# VoidX-Mini-Stomp-X.net
KiCad netlist of a schematic drawn in EasyEDA Pro
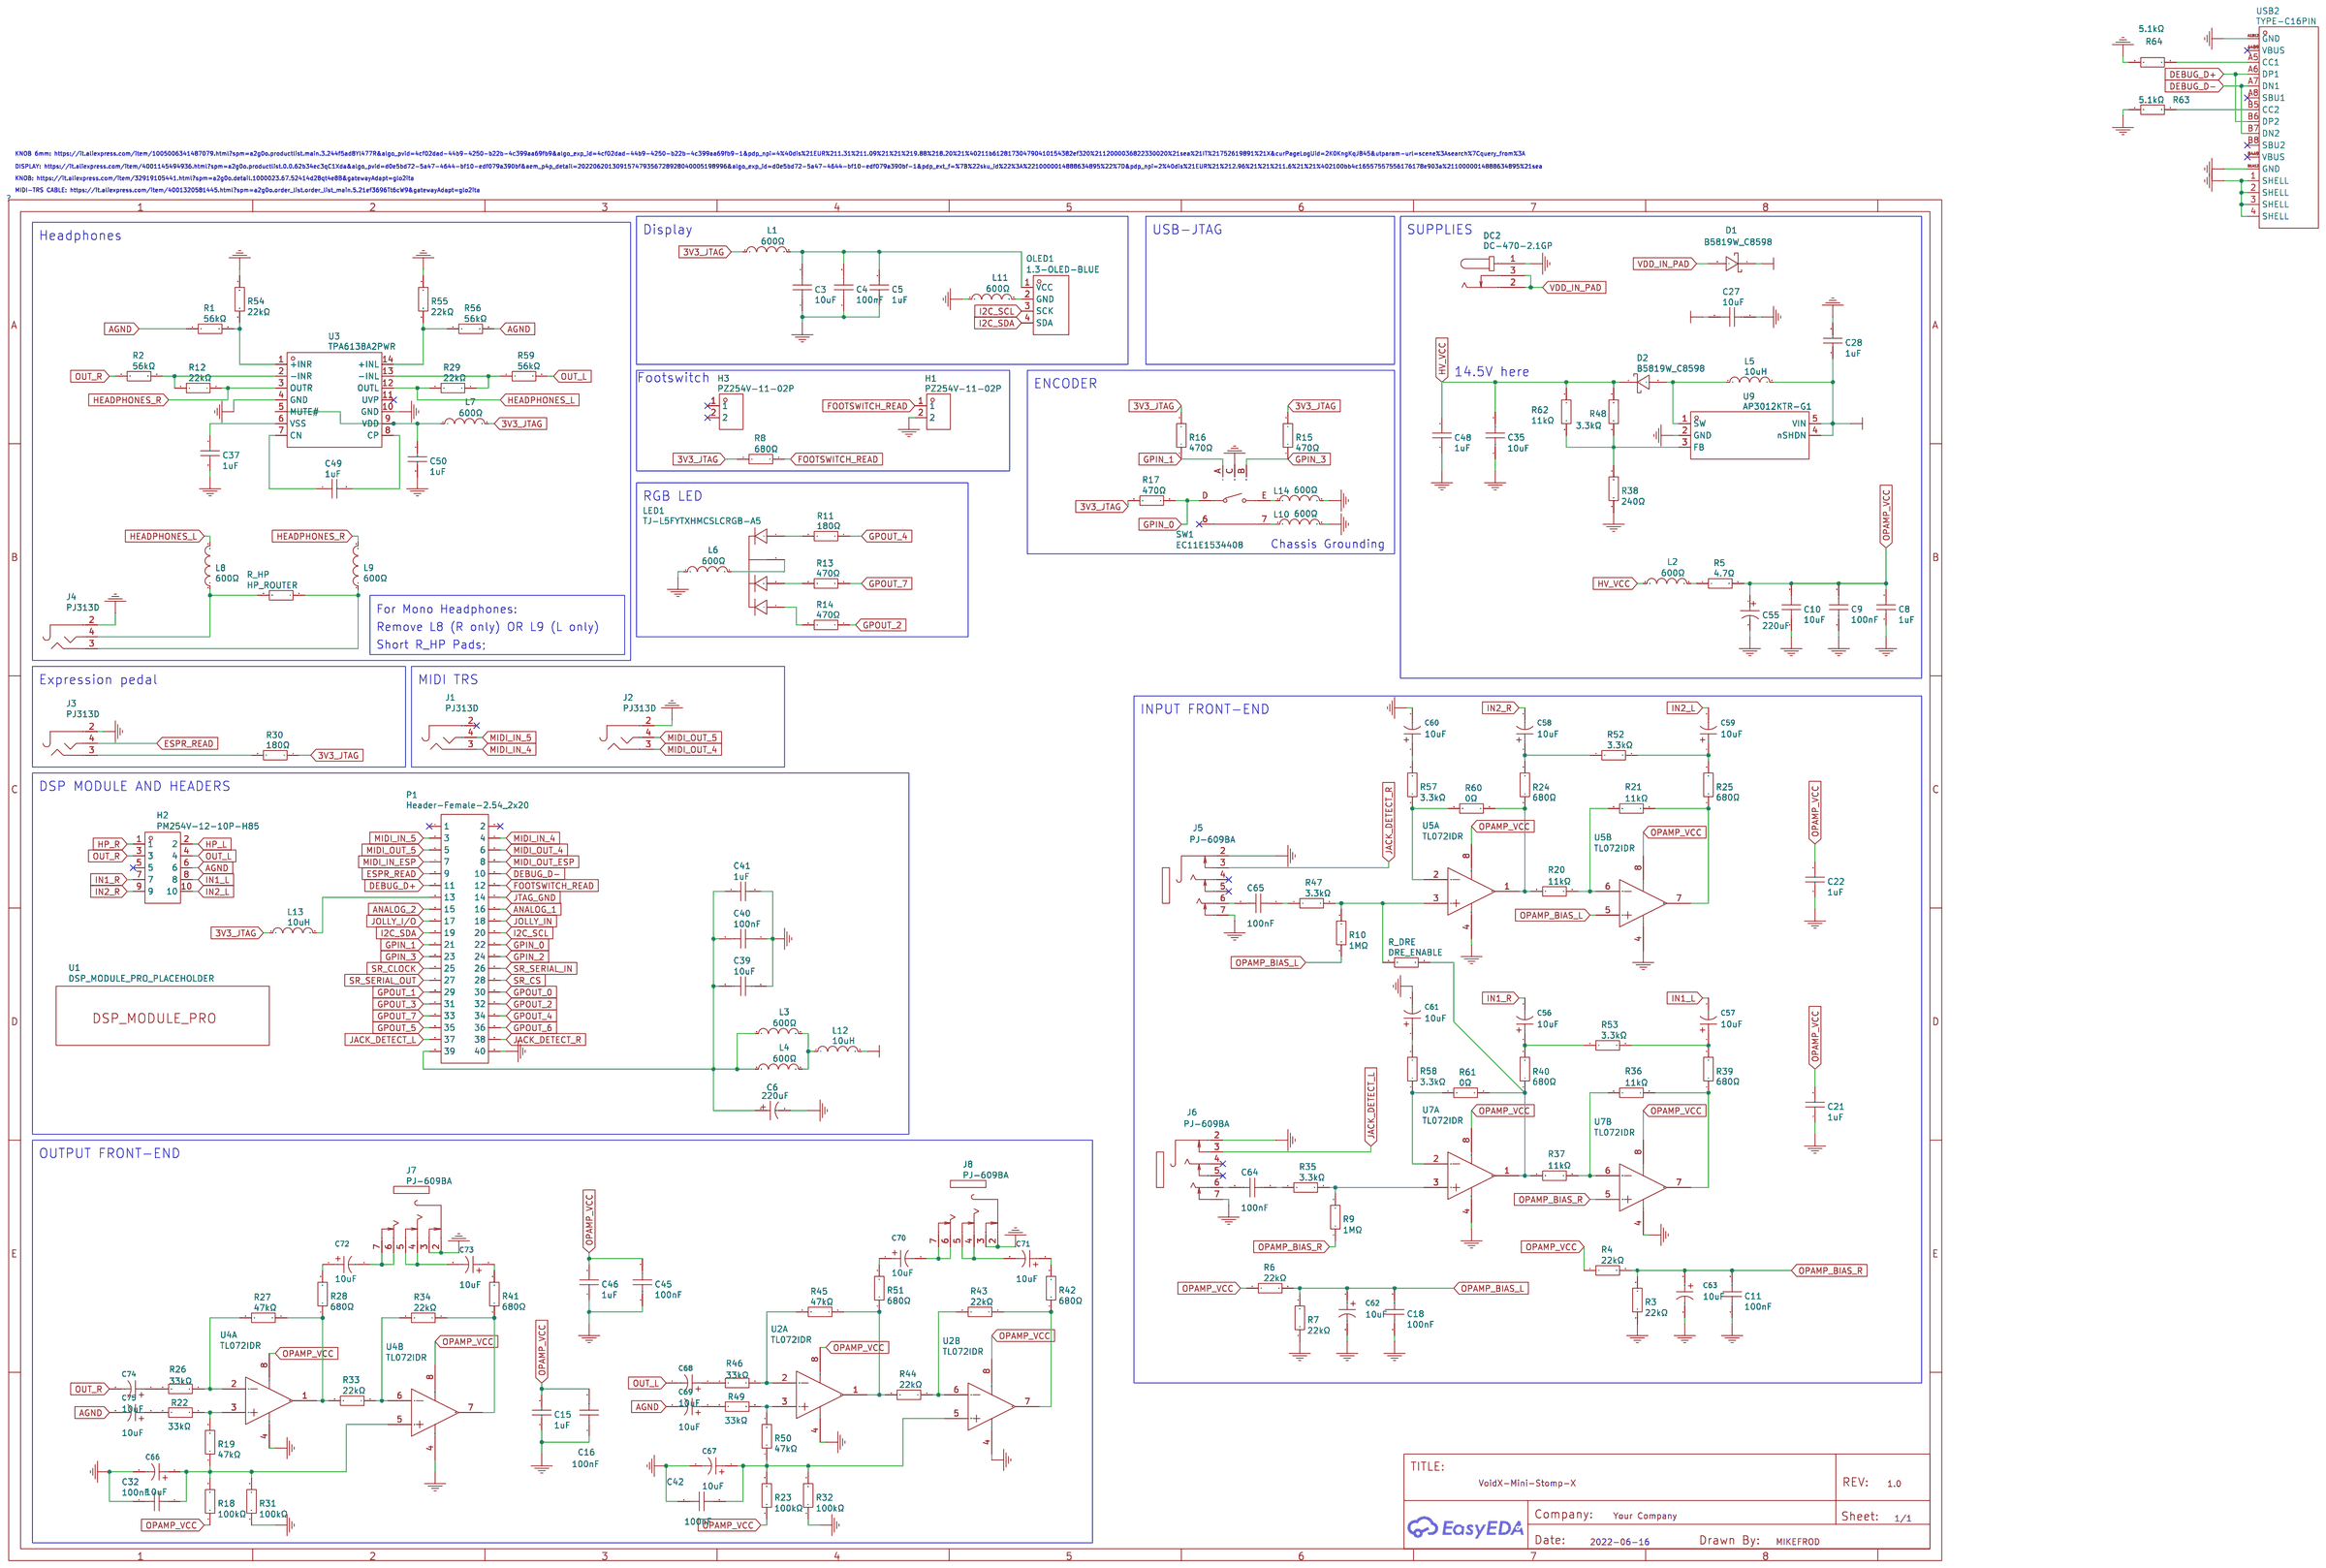
[diagram p0: schematic sheet]

(export (version "E")
  (design (tool "Eeschema 10.0.6"))
  (components
    (comp (ref "C3")
      (value "10uF")
      (footprint "easyedapro:C0603")
      (fields
        (field (name "Manufacturer Part") "CL10A106MA8NRNC")
        (field (name "Manufacturer") "SAMSUNG(三星)")
      )
      (libsource (lib "easyedapro") (part "10uF"))
    )
    (comp (ref "C4")
      (value "100nF")
      (footprint "easyedapro:C0603")
      (fields (field (name "Manufacturer Part") "CC0603KRX7R9BB104") (field (name "Manufacturer") "YAGEO"))
      (libsource (lib "easyedapro") (part "100nF"))
    )
    (comp (ref "C5")
      (value "1uF")
      (footprint "easyedapro:C0603")
      (fields
        (field (name "Manufacturer Part") "CL10A105KB8NNNC")
        (field (name "Manufacturer") "SAMSUNG(三星)")
      )
      (libsource (lib "easyedapro") (part "1uF"))
    )
    (comp (ref "C6")
      (value "220uF")
      (footprint "easyedapro:CAP-SMD_BD6.3-L6.6-W6.6-FD")
      (fields (field (name "Manufacturer Part") "CK1C221M-CRE77") (field (name "Manufacturer") "SEMTECH"))
      (libsource (lib "easyedapro") (part "220uF"))
    )
    (comp (ref "C8")
      (value "1uF")
      (footprint "easyedapro:C0603")
      (fields
        (field (name "Manufacturer Part") "CL10A105KB8NNNC")
        (field (name "Manufacturer") "SAMSUNG(三星)")
      )
      (libsource (lib "easyedapro") (part "1uF"))
    )
    (comp (ref "C9")
      (value "100nF")
      (footprint "easyedapro:C0603")
      (fields (field (name "Manufacturer Part") "CC0603KRX7R9BB104") (field (name "Manufacturer") "YAGEO"))
      (libsource (lib "easyedapro") (part "100nF"))
    )
    (comp (ref "C10")
      (value "10uF")
      (footprint "easyedapro:C0603")
      (fields
        (field (name "Manufacturer Part") "CL10A106MA8NRNC")
        (field (name "Manufacturer") "SAMSUNG(三星)")
      )
      (libsource (lib "easyedapro") (part "10uF"))
    )
    (comp (ref "C11")
      (value "100nF")
      (footprint "easyedapro:C0603")
      (fields (field (name "Manufacturer Part") "CC0603KRX7R9BB104") (field (name "Manufacturer") "YAGEO"))
      (libsource (lib "easyedapro") (part "100nF"))
    )
    (comp (ref "C15")
      (value "1uF")
      (footprint "easyedapro:C0603")
      (fields
        (field (name "Manufacturer Part") "CL10A105KB8NNNC")
        (field (name "Manufacturer") "SAMSUNG(三星)")
      )
      (libsource (lib "easyedapro") (part "1uF"))
    )
    (comp (ref "C16")
      (value "100nF")
      (footprint "easyedapro:C0603")
      (fields (field (name "Manufacturer Part") "CC0603KRX7R9BB104") (field (name "Manufacturer") "YAGEO"))
      (libsource (lib "easyedapro") (part "100nF"))
    )
    (comp (ref "C18")
      (value "100nF")
      (footprint "easyedapro:C0603")
      (fields (field (name "Manufacturer Part") "CC0603KRX7R9BB104") (field (name "Manufacturer") "YAGEO"))
      (libsource (lib "easyedapro") (part "100nF"))
    )
    (comp (ref "C21")
      (value "1uF")
      (footprint "easyedapro:C0603")
      (fields
        (field (name "Manufacturer Part") "CL10A105KB8NNNC")
        (field (name "Manufacturer") "SAMSUNG(三星)")
      )
      (libsource (lib "easyedapro") (part "1uF"))
    )
    (comp (ref "C22")
      (value "1uF")
      (footprint "easyedapro:C0603")
      (fields
        (field (name "Manufacturer Part") "CL10A105KB8NNNC")
        (field (name "Manufacturer") "SAMSUNG(三星)")
      )
      (libsource (lib "easyedapro") (part "1uF"))
    )
    (comp (ref "C27")
      (value "10uF")
      (footprint "easyedapro:C0603")
      (fields
        (field (name "Manufacturer Part") "CL10A106MA8NRNC")
        (field (name "Manufacturer") "SAMSUNG(三星)")
      )
      (libsource (lib "easyedapro") (part "10uF"))
    )
    (comp (ref "C28")
      (value "1uF")
      (footprint "easyedapro:C0603")
      (fields
        (field (name "Manufacturer Part") "CL10A105KB8NNNC")
        (field (name "Manufacturer") "SAMSUNG(三星)")
      )
      (libsource (lib "easyedapro") (part "1uF"))
    )
    (comp (ref "C32")
      (value "100nF")
      (footprint "easyedapro:C0603")
      (fields (field (name "Manufacturer Part") "CC0603KRX7R9BB104") (field (name "Manufacturer") "YAGEO"))
      (libsource (lib "easyedapro") (part "100nF"))
    )
    (comp (ref "C35")
      (value "10uF")
      (footprint "easyedapro:C0603")
      (fields
        (field (name "Manufacturer Part") "CL10A106MA8NRNC")
        (field (name "Manufacturer") "SAMSUNG(三星)")
      )
      (libsource (lib "easyedapro") (part "10uF"))
    )
    (comp (ref "C37")
      (value "1uF")
      (footprint "easyedapro:C0603")
      (fields
        (field (name "Manufacturer Part") "CL10A105KB8NNNC")
        (field (name "Manufacturer") "SAMSUNG(三星)")
      )
      (libsource (lib "easyedapro") (part "1uF"))
    )
    (comp (ref "C39")
      (value "10uF")
      (footprint "easyedapro:C0603")
      (fields
        (field (name "Manufacturer Part") "CL10A106MA8NRNC")
        (field (name "Manufacturer") "SAMSUNG(三星)")
      )
      (libsource (lib "easyedapro") (part "10uF"))
    )
    (comp (ref "C40")
      (value "100nF")
      (footprint "easyedapro:C0603")
      (fields (field (name "Manufacturer Part") "CC0603KRX7R9BB104") (field (name "Manufacturer") "YAGEO"))
      (libsource (lib "easyedapro") (part "100nF"))
    )
    (comp (ref "C41")
      (value "1uF")
      (footprint "easyedapro:C0603")
      (fields
        (field (name "Manufacturer Part") "CL10A105KB8NNNC")
        (field (name "Manufacturer") "SAMSUNG(三星)")
      )
      (libsource (lib "easyedapro") (part "1uF"))
    )
    (comp (ref "C42")
      (value "100nF")
      (footprint "easyedapro:C0603")
      (fields (field (name "Manufacturer Part") "CC0603KRX7R9BB104") (field (name "Manufacturer") "YAGEO"))
      (libsource (lib "easyedapro") (part "100nF"))
    )
    (comp (ref "C45")
      (value "100nF")
      (footprint "easyedapro:C0603")
      (fields (field (name "Manufacturer Part") "CC0603KRX7R9BB104") (field (name "Manufacturer") "YAGEO"))
      (libsource (lib "easyedapro") (part "100nF"))
    )
    (comp (ref "C46")
      (value "1uF")
      (footprint "easyedapro:C0603")
      (fields
        (field (name "Manufacturer Part") "CL10A105KB8NNNC")
        (field (name "Manufacturer") "SAMSUNG(三星)")
      )
      (libsource (lib "easyedapro") (part "1uF"))
    )
    (comp (ref "C48")
      (value "1uF")
      (footprint "easyedapro:C0603")
      (fields
        (field (name "Manufacturer Part") "CL10A105KB8NNNC")
        (field (name "Manufacturer") "SAMSUNG(三星)")
      )
      (libsource (lib "easyedapro") (part "1uF"))
    )
    (comp (ref "C49")
      (value "1uF")
      (footprint "easyedapro:C0603")
      (fields
        (field (name "Manufacturer Part") "CL10A105KB8NNNC")
        (field (name "Manufacturer") "SAMSUNG(三星)")
      )
      (libsource (lib "easyedapro") (part "1uF"))
    )
    (comp (ref "C50")
      (value "1uF")
      (footprint "easyedapro:C0603")
      (fields
        (field (name "Manufacturer Part") "CL10A105KB8NNNC")
        (field (name "Manufacturer") "SAMSUNG(三星)")
      )
      (libsource (lib "easyedapro") (part "1uF"))
    )
    (comp (ref "C55")
      (value "220uF")
      (footprint "easyedapro:CAP-SMD_BD6.3-L6.6-W6.6-FD")
      (fields (field (name "Manufacturer Part") "CK1C221M-CRE77") (field (name "Manufacturer") "SEMTECH"))
      (libsource (lib "easyedapro") (part "220uF"))
    )
    (comp (ref "C56")
      (value "10uF")
      (footprint "easyedapro:CAP-SMD_BD4.0-L4.3-W4.3-LS5.0-FD")
      (fields (field (name "Manufacturer Part") "RVE1C100M0405") (field (name "Manufacturer") "HONOR(荣誉)"))
      (libsource (lib "easyedapro") (part "RVE1C100M0405_C2895765"))
    )
    (comp (ref "C57")
      (value "10uF")
      (footprint "easyedapro:CAP-SMD_BD4.0-L4.3-W4.3-LS5.0-FD")
      (fields (field (name "Manufacturer Part") "RVE1C100M0405") (field (name "Manufacturer") "HONOR(荣誉)"))
      (libsource (lib "easyedapro") (part "RVE1C100M0405_C2895765"))
    )
    (comp (ref "C58")
      (value "10uF")
      (footprint "easyedapro:CAP-SMD_BD4.0-L4.3-W4.3-LS5.0-FD")
      (fields (field (name "Manufacturer Part") "RVE1C100M0405") (field (name "Manufacturer") "HONOR(荣誉)"))
      (libsource (lib "easyedapro") (part "RVE1C100M0405_C2895765"))
    )
    (comp (ref "C59")
      (value "10uF")
      (footprint "easyedapro:CAP-SMD_BD4.0-L4.3-W4.3-LS5.0-FD")
      (fields (field (name "Manufacturer Part") "RVE1C100M0405") (field (name "Manufacturer") "HONOR(荣誉)"))
      (libsource (lib "easyedapro") (part "RVE1C100M0405_C2895765"))
    )
    (comp (ref "C60")
      (value "10uF")
      (footprint "easyedapro:CAP-SMD_BD4.0-L4.3-W4.3-LS5.0-FD")
      (fields (field (name "Manufacturer Part") "RVE1C100M0405") (field (name "Manufacturer") "HONOR(荣誉)"))
      (libsource (lib "easyedapro") (part "RVE1C100M0405_C2895765"))
    )
    (comp (ref "C61")
      (value "10uF")
      (footprint "easyedapro:CAP-SMD_BD4.0-L4.3-W4.3-LS5.0-FD")
      (fields (field (name "Manufacturer Part") "RVE1C100M0405") (field (name "Manufacturer") "HONOR(荣誉)"))
      (libsource (lib "easyedapro") (part "RVE1C100M0405_C2895765"))
    )
    (comp (ref "C62")
      (value "10uF")
      (footprint "easyedapro:CAP-SMD_BD4.0-L4.3-W4.3-LS5.0-FD")
      (fields (field (name "Manufacturer Part") "RVE1C100M0405") (field (name "Manufacturer") "HONOR(荣誉)"))
      (libsource (lib "easyedapro") (part "RVE1C100M0405_C2895765"))
    )
    (comp (ref "C63")
      (value "10uF")
      (footprint "easyedapro:CAP-SMD_BD4.0-L4.3-W4.3-LS5.0-FD")
      (fields (field (name "Manufacturer Part") "RVE1C100M0405") (field (name "Manufacturer") "HONOR(荣誉)"))
      (libsource (lib "easyedapro") (part "RVE1C100M0405_C2895765"))
    )
    (comp (ref "C64")
      (value "100nF")
      (footprint "easyedapro:C1206")
      (fields (field (name "Manufacturer Part") "1206N104J500CT") (field (name "Manufacturer") "Walsin(华新科)"))
      (libsource (lib "easyedapro") (part "1206N104J500"))
    )
    (comp (ref "C65")
      (value "100nF")
      (footprint "easyedapro:C1206")
      (fields (field (name "Manufacturer Part") "1206N104J500CT") (field (name "Manufacturer") "Walsin(华新科)"))
      (libsource (lib "easyedapro") (part "1206N104J500"))
    )
    (comp (ref "C66")
      (value "10uF")
      (footprint "easyedapro:CAP-SMD_BD4.0-L4.3-W4.3-LS5.0-FD")
      (fields (field (name "Manufacturer Part") "RVE1C100M0405") (field (name "Manufacturer") "HONOR(荣誉)"))
      (libsource (lib "easyedapro") (part "RVE1C100M0405_C2895765"))
    )
    (comp (ref "C67")
      (value "10uF")
      (footprint "easyedapro:CAP-SMD_BD4.0-L4.3-W4.3-LS5.0-FD")
      (fields (field (name "Manufacturer Part") "RVE1C100M0405") (field (name "Manufacturer") "HONOR(荣誉)"))
      (libsource (lib "easyedapro") (part "RVE1C100M0405_C2895765"))
    )
    (comp (ref "C68")
      (value "10uF")
      (footprint "easyedapro:CAP-SMD_BD4.0-L4.3-W4.3-LS5.0-FD")
      (fields (field (name "Manufacturer Part") "RVE1C100M0405") (field (name "Manufacturer") "HONOR(荣誉)"))
      (libsource (lib "easyedapro") (part "RVE1C100M0405_C2895765"))
    )
    (comp (ref "C69")
      (value "10uF")
      (footprint "easyedapro:CAP-SMD_BD4.0-L4.3-W4.3-LS5.0-FD")
      (fields (field (name "Manufacturer Part") "RVE1C100M0405") (field (name "Manufacturer") "HONOR(荣誉)"))
      (libsource (lib "easyedapro") (part "RVE1C100M0405_C2895765"))
    )
    (comp (ref "C70")
      (value "10uF")
      (footprint "easyedapro:CAP-SMD_BD4.0-L4.3-W4.3-LS5.0-FD")
      (fields (field (name "Manufacturer Part") "RVE1C100M0405") (field (name "Manufacturer") "HONOR(荣誉)"))
      (libsource (lib "easyedapro") (part "RVE1C100M0405_C2895765"))
    )
    (comp (ref "C71")
      (value "10uF")
      (footprint "easyedapro:CAP-SMD_BD4.0-L4.3-W4.3-LS5.0-FD")
      (fields (field (name "Manufacturer Part") "RVE1C100M0405") (field (name "Manufacturer") "HONOR(荣誉)"))
      (libsource (lib "easyedapro") (part "RVE1C100M0405_C2895765"))
    )
    (comp (ref "C72")
      (value "10uF")
      (footprint "easyedapro:CAP-SMD_BD4.0-L4.3-W4.3-LS5.0-FD")
      (fields (field (name "Manufacturer Part") "RVE1C100M0405") (field (name "Manufacturer") "HONOR(荣誉)"))
      (libsource (lib "easyedapro") (part "RVE1C100M0405_C2895765"))
    )
    (comp (ref "C73")
      (value "10uF")
      (footprint "easyedapro:CAP-SMD_BD4.0-L4.3-W4.3-LS5.0-FD")
      (fields (field (name "Manufacturer Part") "RVE1C100M0405") (field (name "Manufacturer") "HONOR(荣誉)"))
      (libsource (lib "easyedapro") (part "RVE1C100M0405_C2895765"))
    )
    (comp (ref "C74")
      (value "10uF")
      (footprint "easyedapro:CAP-SMD_BD4.0-L4.3-W4.3-LS5.0-FD")
      (fields (field (name "Manufacturer Part") "RVE1C100M0405") (field (name "Manufacturer") "HONOR(荣誉)"))
      (libsource (lib "easyedapro") (part "RVE1C100M0405_C2895765"))
    )
    (comp (ref "C75")
      (value "10uF")
      (footprint "easyedapro:CAP-SMD_BD4.0-L4.3-W4.3-LS5.0-FD")
      (fields (field (name "Manufacturer Part") "RVE1C100M0405") (field (name "Manufacturer") "HONOR(荣誉)"))
      (libsource (lib "easyedapro") (part "RVE1C100M0405_C2895765"))
    )
    (comp (ref "D1")
      (value "B5819W_C8598")
      (footprint "easyedapro:SOD-123_L2.7-W1.6-LS3.7-RD-1")
      (fields (field (name "Manufacturer Part") "B5819W") (field (name "Manufacturer") "CJ"))
      (libsource (lib "easyedapro") (part "B5819W_C8598"))
    )
    (comp (ref "D2")
      (value "B5819W_C8598")
      (footprint "easyedapro:SOD-123_L2.7-W1.6-LS3.7-RD-1")
      (fields (field (name "Manufacturer Part") "B5819W") (field (name "Manufacturer") "CJ"))
      (libsource (lib "easyedapro") (part "B5819W_C8598"))
    )
    (comp (ref "DC2")
      (value "DC-470-2.1GP")
      (footprint "easyedapro:DC-IN-TH_DC-470-2.1GP")
      (fields (field (name "Manufacturer") "GANGYUAN"))
      (libsource (lib "easyedapro") (part "DC-470-2.1GP"))
    )
    (comp (ref "H1")
      (value "PZ254V-11-02P")
      (footprint "easyedapro:HDR-TH_2P-P2.54-V-M")
      (libsource (lib "easyedapro") (part "PZ254V-11-02P"))
    )
    (comp (ref "H2")
      (value "PM254V-12-10P-H85")
      (footprint "easyedapro:HDR-TH_10P-P2.54-V-F-R2-C5-S2.54")
      (fields (field (name "Manufacturer") "XFCN"))
      (libsource (lib "easyedapro") (part "PM254V-12-10P-H85"))
    )
    (comp (ref "H3")
      (value "PZ254V-11-02P")
      (footprint "easyedapro:HDR-TH_2P-P2.54-V-M")
      (libsource (lib "easyedapro") (part "PZ254V-11-02P"))
    )
    (comp (ref "J1")
      (value "PJ313D")
      (footprint "easyedapro:AUDIO-TH_PJ313D")
      (fields (field (name "Manufacturer") "BOOMELE"))
      (libsource (lib "easyedapro") (part "PJ313D"))
    )
    (comp (ref "J2")
      (value "PJ313D")
      (footprint "easyedapro:AUDIO-TH_PJ313D")
      (fields (field (name "Manufacturer") "BOOMELE"))
      (libsource (lib "easyedapro") (part "PJ313D"))
    )
    (comp (ref "J3")
      (value "PJ313D")
      (footprint "easyedapro:AUDIO-TH_PJ313D")
      (fields (field (name "Manufacturer") "BOOMELE"))
      (libsource (lib "easyedapro") (part "PJ313D"))
    )
    (comp (ref "J4")
      (value "PJ313D")
      (footprint "easyedapro:AUDIO-TH_PJ313D")
      (fields (field (name "Manufacturer") "BOOMELE"))
      (libsource (lib "easyedapro") (part "PJ313D"))
    )
    (comp (ref "J5")
      (value "PJ-609BA")
      (footprint "easyedapro:AUDIO-TH_PJ-609BA")
      (fields (field (name "Manufacturer") "HOOYA(皓宇电子)"))
      (libsource (lib "easyedapro") (part "PJ-609BA"))
    )
    (comp (ref "J6")
      (value "PJ-609BA")
      (footprint "easyedapro:AUDIO-TH_PJ-609BA")
      (fields (field (name "Manufacturer") "HOOYA(皓宇电子)"))
      (libsource (lib "easyedapro") (part "PJ-609BA"))
    )
    (comp (ref "J7")
      (value "PJ-609BA")
      (footprint "easyedapro:AUDIO-TH_PJ-609BA")
      (fields (field (name "Manufacturer") "HOOYA(皓宇电子)"))
      (libsource (lib "easyedapro") (part "PJ-609BA"))
    )
    (comp (ref "J8")
      (value "PJ-609BA")
      (footprint "easyedapro:AUDIO-TH_PJ-609BA")
      (fields (field (name "Manufacturer") "HOOYA(皓宇电子)"))
      (libsource (lib "easyedapro") (part "PJ-609BA"))
    )
    (comp (ref "L1")
      (value "600Ω")
      (footprint "easyedapro:L0603")
      (fields (field (name "Manufacturer Part") "GZ1608D601TF") (field (name "Manufacturer") "Sunlord(顺络)"))
      (libsource (lib "easyedapro") (part "600Ω"))
    )
    (comp (ref "L2")
      (value "600Ω")
      (footprint "easyedapro:L0603")
      (fields (field (name "Manufacturer Part") "GZ1608D601TF") (field (name "Manufacturer") "Sunlord(顺络)"))
      (libsource (lib "easyedapro") (part "600Ω"))
    )
    (comp (ref "L3")
      (value "600Ω")
      (footprint "easyedapro:L0603")
      (fields (field (name "Manufacturer Part") "GZ1608D601TF") (field (name "Manufacturer") "Sunlord(顺络)"))
      (libsource (lib "easyedapro") (part "600Ω"))
    )
    (comp (ref "L4")
      (value "600Ω")
      (footprint "easyedapro:L0603")
      (fields (field (name "Manufacturer Part") "GZ1608D601TF") (field (name "Manufacturer") "Sunlord(顺络)"))
      (libsource (lib "easyedapro") (part "600Ω"))
    )
    (comp (ref "L5")
      (value "10uH")
      (footprint "easyedapro:IND-SMD_L4.0-W4.0")
      (fields (field (name "Manufacturer Part") "SWPA4030S100MT") (field (name "Manufacturer") "Sunlord"))
      (libsource (lib "easyedapro") (part "10uH"))
    )
    (comp (ref "L6")
      (value "600Ω")
      (footprint "easyedapro:L0603")
      (fields (field (name "Manufacturer Part") "GZ1608D601TF") (field (name "Manufacturer") "Sunlord(顺络)"))
      (libsource (lib "easyedapro") (part "600Ω"))
    )
    (comp (ref "L7")
      (value "600Ω")
      (footprint "easyedapro:L0603")
      (fields (field (name "Manufacturer Part") "GZ1608D601TF") (field (name "Manufacturer") "Sunlord(顺络)"))
      (libsource (lib "easyedapro") (part "600Ω"))
    )
    (comp (ref "L8")
      (value "600Ω")
      (footprint "easyedapro:L0603")
      (fields (field (name "Manufacturer Part") "GZ1608D601TF") (field (name "Manufacturer") "Sunlord(顺络)"))
      (libsource (lib "easyedapro") (part "600Ω"))
    )
    (comp (ref "L9")
      (value "600Ω")
      (footprint "easyedapro:L0603")
      (fields (field (name "Manufacturer Part") "GZ1608D601TF") (field (name "Manufacturer") "Sunlord(顺络)"))
      (libsource (lib "easyedapro") (part "600Ω"))
    )
    (comp (ref "L10")
      (value "600Ω")
      (footprint "easyedapro:L0603")
      (fields (field (name "Manufacturer Part") "GZ1608D601TF") (field (name "Manufacturer") "Sunlord(顺络)"))
      (libsource (lib "easyedapro") (part "600Ω"))
    )
    (comp (ref "L11")
      (value "600Ω")
      (footprint "easyedapro:L0603")
      (fields (field (name "Manufacturer Part") "GZ1608D601TF") (field (name "Manufacturer") "Sunlord(顺络)"))
      (libsource (lib "easyedapro") (part "600Ω"))
    )
    (comp (ref "L12")
      (value "10uH")
      (footprint "easyedapro:IND-SMD_L4.0-W4.0")
      (fields (field (name "Manufacturer Part") "SWPA4030S100MT") (field (name "Manufacturer") "Sunlord"))
      (libsource (lib "easyedapro") (part "10uH"))
    )
    (comp (ref "L13")
      (value "10uH")
      (footprint "easyedapro:IND-SMD_L4.0-W4.0")
      (fields (field (name "Manufacturer Part") "SWPA4030S100MT") (field (name "Manufacturer") "Sunlord"))
      (libsource (lib "easyedapro") (part "10uH"))
    )
    (comp (ref "L14")
      (value "600Ω")
      (footprint "easyedapro:L0603")
      (fields (field (name "Manufacturer Part") "GZ1608D601TF") (field (name "Manufacturer") "Sunlord(顺络)"))
      (libsource (lib "easyedapro") (part "600Ω"))
    )
    (comp (ref "LED1")
      (value "TJ-L5FYTXHMCSLCRGB-A5")
      (footprint "easyedapro:LED-TH_4P-BD5.8-P1.30")
      (fields (field (name "Manufacturer") "TOGIALED(统佳)"))
      (libsource (lib "easyedapro") (part "TJ-L5FYTXHMCSLCRGB-A5"))
    )
    (comp (ref "OLED1")
      (value "1.3-OLED-BLUE")
      (footprint "easyedapro:1.3-OLED-BLUE")
      (libsource (lib "easyedapro") (part "1.3-OLED-BLUE"))
    )
    (comp (ref "P1")
      (value "Header-Female-2.54_2x20")
      (footprint "easyedapro:HDR-TH_40P-P2.54-V-F-R2-C20-S2.54")
      (fields
        (field (name "Manufacturer Part") "2.54mm 2*20PFemale header")
        (field (name "Manufacturer") "ZHOURI(洲日)")
      )
      (libsource (lib "easyedapro") (part "Header-Female-2.54_2x20"))
    )
    (comp (ref "R1")
      (value "56kΩ")
      (footprint "easyedapro:R0603")
      (fields
        (field (name "Manufacturer Part") "0603WAF5602T5E")
        (field (name "Manufacturer") "UNI-ROYAL(厚声)")
      )
      (libsource (lib "easyedapro") (part "56kΩ"))
    )
    (comp (ref "R2")
      (value "56kΩ")
      (footprint "easyedapro:R0603")
      (fields
        (field (name "Manufacturer Part") "0603WAF5602T5E")
        (field (name "Manufacturer") "UNI-ROYAL(厚声)")
      )
      (libsource (lib "easyedapro") (part "56kΩ"))
    )
    (comp (ref "R3")
      (value "22kΩ")
      (footprint "easyedapro:R0603")
      (fields (field (name "Manufacturer Part") "0603WAF2202T5E") (field (name "Manufacturer") "UniOhm"))
      (libsource (lib "easyedapro") (part "22kΩ"))
    )
    (comp (ref "R4")
      (value "22kΩ")
      (footprint "easyedapro:R0603")
      (fields (field (name "Manufacturer Part") "0603WAF2202T5E") (field (name "Manufacturer") "UniOhm"))
      (libsource (lib "easyedapro") (part "22kΩ"))
    )
    (comp (ref "R5")
      (value "4.7Ω")
      (footprint "easyedapro:R0603")
      (fields (field (name "Manufacturer Part") "0603WAF470KT5E") (field (name "Manufacturer") "UniOhm"))
      (libsource (lib "easyedapro") (part "4.7Ω"))
    )
    (comp (ref "R6")
      (value "22kΩ")
      (footprint "easyedapro:R0603")
      (fields (field (name "Manufacturer Part") "0603WAF2202T5E") (field (name "Manufacturer") "UniOhm"))
      (libsource (lib "easyedapro") (part "22kΩ"))
    )
    (comp (ref "R7")
      (value "22kΩ")
      (footprint "easyedapro:R0603")
      (fields (field (name "Manufacturer Part") "0603WAF2202T5E") (field (name "Manufacturer") "UniOhm"))
      (libsource (lib "easyedapro") (part "22kΩ"))
    )
    (comp (ref "R8")
      (value "680Ω")
      (footprint "easyedapro:R0603")
      (fields (field (name "Manufacturer Part") "0603WAF6800T5E") (field (name "Manufacturer") "UniOhm"))
      (libsource (lib "easyedapro") (part "680Ω"))
    )
    (comp (ref "R9")
      (value "1MΩ")
      (footprint "easyedapro:R0603")
      (fields
        (field (name "Manufacturer Part") "0603WAF1004T5E")
        (field (name "Manufacturer") "UNI-ROYAL(厚声)")
      )
      (libsource (lib "easyedapro") (part "1MΩ"))
    )
    (comp (ref "R10")
      (value "1MΩ")
      (footprint "easyedapro:R0603")
      (fields
        (field (name "Manufacturer Part") "0603WAF1004T5E")
        (field (name "Manufacturer") "UNI-ROYAL(厚声)")
      )
      (libsource (lib "easyedapro") (part "1MΩ"))
    )
    (comp (ref "R11")
      (value "180Ω")
      (footprint "easyedapro:R0603")
      (fields (field (name "Manufacturer Part") "0603WAF1800T5E") (field (name "Manufacturer") "UniOhm"))
      (libsource (lib "easyedapro") (part "180Ω"))
    )
    (comp (ref "R12")
      (value "22kΩ")
      (footprint "easyedapro:R0603")
      (fields
        (field (name "Manufacturer Part") "0603WAF2202T5E")
        (field (name "Manufacturer") "UNI-ROYAL(厚声)")
      )
      (libsource (lib "easyedapro") (part "47kΩ"))
    )
    (comp (ref "R13")
      (value "470Ω")
      (footprint "easyedapro:R0603")
      (fields (field (name "Manufacturer Part") "0603WAF4700T5E") (field (name "Manufacturer") "UniOhm"))
      (libsource (lib "easyedapro") (part "470Ω"))
    )
    (comp (ref "R14")
      (value "470Ω")
      (footprint "easyedapro:R0603")
      (fields (field (name "Manufacturer Part") "0603WAF4700T5E") (field (name "Manufacturer") "UniOhm"))
      (libsource (lib "easyedapro") (part "470Ω"))
    )
    (comp (ref "R15")
      (value "470Ω")
      (footprint "easyedapro:R0603")
      (fields (field (name "Manufacturer Part") "0603WAF4700T5E") (field (name "Manufacturer") "UniOhm"))
      (libsource (lib "easyedapro") (part "470Ω"))
    )
    (comp (ref "R16")
      (value "470Ω")
      (footprint "easyedapro:R0603")
      (fields (field (name "Manufacturer Part") "0603WAF4700T5E") (field (name "Manufacturer") "UniOhm"))
      (libsource (lib "easyedapro") (part "470Ω"))
    )
    (comp (ref "R17")
      (value "470Ω")
      (footprint "easyedapro:R0603")
      (fields (field (name "Manufacturer Part") "0603WAF4700T5E") (field (name "Manufacturer") "UniOhm"))
      (libsource (lib "easyedapro") (part "470Ω"))
    )
    (comp (ref "R18")
      (value "100kΩ")
      (footprint "easyedapro:R0603")
      (fields
        (field (name "Manufacturer Part") "0603WAF1003T5E")
        (field (name "Manufacturer") "UNI-ROYAL(厚声)")
      )
      (libsource (lib "easyedapro") (part "100kΩ"))
    )
    (comp (ref "R19")
      (value "47kΩ")
      (footprint "easyedapro:R0603")
      (fields
        (field (name "Manufacturer Part") "0603WAF4702T5E")
        (field (name "Manufacturer") "UNI-ROYAL(厚声)")
      )
      (libsource (lib "easyedapro") (part "47kΩ"))
    )
    (comp (ref "R20")
      (value "11kΩ")
      (footprint "easyedapro:R0603")
      (fields (field (name "Manufacturer Part") "0603WAF1102T5E") (field (name "Manufacturer") "UniOhm"))
      (libsource (lib "easyedapro") (part "11kΩ"))
    )
    (comp (ref "R21")
      (value "11kΩ")
      (footprint "easyedapro:R0603")
      (fields (field (name "Manufacturer Part") "0603WAF1102T5E") (field (name "Manufacturer") "UniOhm"))
      (libsource (lib "easyedapro") (part "11kΩ"))
    )
    (comp (ref "R22")
      (value "33kΩ")
      (footprint "easyedapro:R0603")
      (fields
        (field (name "Manufacturer Part") "0603WAF3302T5E")
        (field (name "Manufacturer") "UNI-ROYAL(厚声)")
      )
      (libsource (lib "easyedapro") (part "33kΩ"))
    )
    (comp (ref "R23")
      (value "100kΩ")
      (footprint "easyedapro:R0603")
      (fields
        (field (name "Manufacturer Part") "0603WAF1003T5E")
        (field (name "Manufacturer") "UNI-ROYAL(厚声)")
      )
      (libsource (lib "easyedapro") (part "100kΩ"))
    )
    (comp (ref "R24")
      (value "680Ω")
      (footprint "easyedapro:R0603")
      (fields (field (name "Manufacturer Part") "0603WAF6800T5E") (field (name "Manufacturer") "UniOhm"))
      (libsource (lib "easyedapro") (part "680Ω"))
    )
    (comp (ref "R25")
      (value "680Ω")
      (footprint "easyedapro:R0603")
      (fields (field (name "Manufacturer Part") "0603WAF6800T5E") (field (name "Manufacturer") "UniOhm"))
      (libsource (lib "easyedapro") (part "680Ω"))
    )
    (comp (ref "R26")
      (value "33kΩ")
      (footprint "easyedapro:R0603")
      (fields
        (field (name "Manufacturer Part") "0603WAF3302T5E")
        (field (name "Manufacturer") "UNI-ROYAL(厚声)")
      )
      (libsource (lib "easyedapro") (part "33kΩ"))
    )
    (comp (ref "R27")
      (value "47kΩ")
      (footprint "easyedapro:R0603")
      (fields
        (field (name "Manufacturer Part") "0603WAF4702T5E")
        (field (name "Manufacturer") "UNI-ROYAL(厚声)")
      )
      (libsource (lib "easyedapro") (part "47kΩ"))
    )
    (comp (ref "R28")
      (value "680Ω")
      (footprint "easyedapro:R0603")
      (fields (field (name "Manufacturer Part") "0603WAF6800T5E") (field (name "Manufacturer") "UniOhm"))
      (libsource (lib "easyedapro") (part "680Ω"))
    )
    (comp (ref "R29")
      (value "22kΩ")
      (footprint "easyedapro:R0603")
      (fields
        (field (name "Manufacturer Part") "0603WAF2202T5E")
        (field (name "Manufacturer") "UNI-ROYAL(厚声)")
      )
      (libsource (lib "easyedapro") (part "47kΩ"))
    )
    (comp (ref "R30")
      (value "180Ω")
      (footprint "easyedapro:R0603")
      (fields (field (name "Manufacturer Part") "0603WAF1800T5E") (field (name "Manufacturer") "UniOhm"))
      (libsource (lib "easyedapro") (part "180Ω"))
    )
    (comp (ref "R31")
      (value "100kΩ")
      (footprint "easyedapro:R0603")
      (fields
        (field (name "Manufacturer Part") "0603WAF1003T5E")
        (field (name "Manufacturer") "UNI-ROYAL(厚声)")
      )
      (libsource (lib "easyedapro") (part "100kΩ"))
    )
    (comp (ref "R32")
      (value "100kΩ")
      (footprint "easyedapro:R0603")
      (fields
        (field (name "Manufacturer Part") "0603WAF1003T5E")
        (field (name "Manufacturer") "UNI-ROYAL(厚声)")
      )
      (libsource (lib "easyedapro") (part "100kΩ"))
    )
    (comp (ref "R33")
      (value "22kΩ")
      (footprint "easyedapro:R0603")
      (fields (field (name "Manufacturer Part") "0603WAF2202T5E") (field (name "Manufacturer") "UniOhm"))
      (libsource (lib "easyedapro") (part "22kΩ"))
    )
    (comp (ref "R34")
      (value "22kΩ")
      (footprint "easyedapro:R0603")
      (fields (field (name "Manufacturer Part") "0603WAF2202T5E") (field (name "Manufacturer") "UniOhm"))
      (libsource (lib "easyedapro") (part "22kΩ"))
    )
    (comp (ref "R35")
      (value "3.3kΩ")
      (footprint "easyedapro:R0603_NEW")
      (fields
        (field (name "Manufacturer Part") "0603WAF3301T5E")
        (field (name "Manufacturer") "UNI-ROYAL(厚声)")
      )
      (libsource (lib "easyedapro") (part "3.3kΩ"))
    )
    (comp (ref "R36")
      (value "11kΩ")
      (footprint "easyedapro:R0603")
      (fields (field (name "Manufacturer Part") "0603WAF1102T5E") (field (name "Manufacturer") "UniOhm"))
      (libsource (lib "easyedapro") (part "11kΩ"))
    )
    (comp (ref "R37")
      (value "11kΩ")
      (footprint "easyedapro:R0603")
      (fields (field (name "Manufacturer Part") "0603WAF1102T5E") (field (name "Manufacturer") "UniOhm"))
      (libsource (lib "easyedapro") (part "11kΩ"))
    )
    (comp (ref "R38")
      (value "240Ω")
      (footprint "easyedapro:R0603")
      (fields
        (field (name "Manufacturer Part") "0603WAF2400T5E")
        (field (name "Manufacturer") "UNI-ROYAL(厚声)")
      )
      (libsource (lib "easyedapro") (part "240Ω"))
    )
    (comp (ref "R39")
      (value "680Ω")
      (footprint "easyedapro:R0603")
      (fields (field (name "Manufacturer Part") "0603WAF6800T5E") (field (name "Manufacturer") "UniOhm"))
      (libsource (lib "easyedapro") (part "680Ω"))
    )
    (comp (ref "R40")
      (value "680Ω")
      (footprint "easyedapro:R0603")
      (fields (field (name "Manufacturer Part") "0603WAF6800T5E") (field (name "Manufacturer") "UniOhm"))
      (libsource (lib "easyedapro") (part "680Ω"))
    )
    (comp (ref "R41")
      (value "680Ω")
      (footprint "easyedapro:R0603")
      (fields (field (name "Manufacturer Part") "0603WAF6800T5E") (field (name "Manufacturer") "UniOhm"))
      (libsource (lib "easyedapro") (part "680Ω"))
    )
    (comp (ref "R42")
      (value "680Ω")
      (footprint "easyedapro:R0603")
      (fields (field (name "Manufacturer Part") "0603WAF6800T5E") (field (name "Manufacturer") "UniOhm"))
      (libsource (lib "easyedapro") (part "680Ω"))
    )
    (comp (ref "R43")
      (value "22kΩ")
      (footprint "easyedapro:R0603")
      (fields (field (name "Manufacturer Part") "0603WAF2202T5E") (field (name "Manufacturer") "UniOhm"))
      (libsource (lib "easyedapro") (part "22kΩ"))
    )
    (comp (ref "R44")
      (value "22kΩ")
      (footprint "easyedapro:R0603")
      (fields (field (name "Manufacturer Part") "0603WAF2202T5E") (field (name "Manufacturer") "UniOhm"))
      (libsource (lib "easyedapro") (part "22kΩ"))
    )
    (comp (ref "R45")
      (value "47kΩ")
      (footprint "easyedapro:R0603")
      (fields
        (field (name "Manufacturer Part") "0603WAF4702T5E")
        (field (name "Manufacturer") "UNI-ROYAL(厚声)")
      )
      (libsource (lib "easyedapro") (part "47kΩ"))
    )
    (comp (ref "R46")
      (value "33kΩ")
      (footprint "easyedapro:R0603")
      (fields
        (field (name "Manufacturer Part") "0603WAF3302T5E")
        (field (name "Manufacturer") "UNI-ROYAL(厚声)")
      )
      (libsource (lib "easyedapro") (part "33kΩ"))
    )
    (comp (ref "R47")
      (value "3.3kΩ")
      (footprint "easyedapro:R0603_NEW")
      (fields
        (field (name "Manufacturer Part") "0603WAF3301T5E")
        (field (name "Manufacturer") "UNI-ROYAL(厚声)")
      )
      (libsource (lib "easyedapro") (part "3.3kΩ"))
    )
    (comp (ref "R48")
      (value "3.3kΩ")
      (footprint "easyedapro:R0603_NEW")
      (fields (field (name "Manufacturer Part") "0603WAF3301T5E") (field (name "Manufacturer") "UniOhm"))
      (libsource (lib "easyedapro") (part "3.3kΩ"))
    )
    (comp (ref "R49")
      (value "33kΩ")
      (footprint "easyedapro:R0603")
      (fields
        (field (name "Manufacturer Part") "0603WAF3302T5E")
        (field (name "Manufacturer") "UNI-ROYAL(厚声)")
      )
      (libsource (lib "easyedapro") (part "33kΩ"))
    )
    (comp (ref "R50")
      (value "47kΩ")
      (footprint "easyedapro:R0603")
      (fields
        (field (name "Manufacturer Part") "0603WAF4702T5E")
        (field (name "Manufacturer") "UNI-ROYAL(厚声)")
      )
      (libsource (lib "easyedapro") (part "47kΩ"))
    )
    (comp (ref "R51")
      (value "680Ω")
      (footprint "easyedapro:R0603")
      (fields (field (name "Manufacturer Part") "0603WAF6800T5E") (field (name "Manufacturer") "UniOhm"))
      (libsource (lib "easyedapro") (part "680Ω"))
    )
    (comp (ref "R52")
      (value "3.3kΩ")
      (footprint "easyedapro:R0603_NEW")
      (fields
        (field (name "Manufacturer Part") "0603WAF3301T5E")
        (field (name "Manufacturer") "UNI-ROYAL(厚声)")
      )
      (libsource (lib "easyedapro") (part "3.3kΩ"))
    )
    (comp (ref "R53")
      (value "3.3kΩ")
      (footprint "easyedapro:R0603_NEW")
      (fields
        (field (name "Manufacturer Part") "0603WAF3301T5E")
        (field (name "Manufacturer") "UNI-ROYAL(厚声)")
      )
      (libsource (lib "easyedapro") (part "3.3kΩ"))
    )
    (comp (ref "R54")
      (value "22kΩ")
      (footprint "easyedapro:R0603")
      (fields
        (field (name "Manufacturer Part") "0603WAF2202T5E")
        (field (name "Manufacturer") "UNI-ROYAL(厚声)")
      )
      (libsource (lib "easyedapro") (part "47kΩ"))
    )
    (comp (ref "R55")
      (value "22kΩ")
      (footprint "easyedapro:R0603")
      (fields
        (field (name "Manufacturer Part") "0603WAF2202T5E")
        (field (name "Manufacturer") "UNI-ROYAL(厚声)")
      )
      (libsource (lib "easyedapro") (part "47kΩ"))
    )
    (comp (ref "R56")
      (value "56kΩ")
      (footprint "easyedapro:R0603")
      (fields
        (field (name "Manufacturer Part") "0603WAF5602T5E")
        (field (name "Manufacturer") "UNI-ROYAL(厚声)")
      )
      (libsource (lib "easyedapro") (part "56kΩ"))
    )
    (comp (ref "R57")
      (value "3.3kΩ")
      (footprint "easyedapro:R0603_NEW")
      (fields
        (field (name "Manufacturer Part") "0603WAF3301T5E")
        (field (name "Manufacturer") "UNI-ROYAL(厚声)")
      )
      (libsource (lib "easyedapro") (part "3.3kΩ"))
    )
    (comp (ref "R58")
      (value "3.3kΩ")
      (footprint "easyedapro:R0603_NEW")
      (fields
        (field (name "Manufacturer Part") "0603WAF3301T5E")
        (field (name "Manufacturer") "UNI-ROYAL(厚声)")
      )
      (libsource (lib "easyedapro") (part "3.3kΩ"))
    )
    (comp (ref "R59")
      (value "56kΩ")
      (footprint "easyedapro:R0603")
      (fields
        (field (name "Manufacturer Part") "0603WAF5602T5E")
        (field (name "Manufacturer") "UNI-ROYAL(厚声)")
      )
      (libsource (lib "easyedapro") (part "56kΩ"))
    )
    (comp (ref "R60")
      (value "0Ω")
      (footprint "easyedapro:R0805")
      (fields
        (field (name "Manufacturer Part") "0805W8F0000T5E")
        (field (name "Manufacturer") "UNI-ROYAL(厚声)")
      )
      (libsource (lib "easyedapro") (part "0Ω"))
    )
    (comp (ref "R61")
      (value "0Ω")
      (footprint "easyedapro:R0805")
      (fields
        (field (name "Manufacturer Part") "0805W8F0000T5E")
        (field (name "Manufacturer") "UNI-ROYAL(厚声)")
      )
      (libsource (lib "easyedapro") (part "0Ω"))
    )
    (comp (ref "R62")
      (value "11kΩ")
      (footprint "easyedapro:R0603")
      (fields (field (name "Manufacturer Part") "0603WAF1102T5E") (field (name "Manufacturer") "UniOhm"))
      (libsource (lib "easyedapro") (part "11kΩ"))
    )
    (comp (ref "R63")
      (value "5.1kΩ")
      (footprint "easyedapro:R0603")
      (fields
        (field (name "Manufacturer Part") "0603WAF5101T5E")
        (field (name "Manufacturer") "UNI-ROYAL(厚声)")
      )
      (libsource (lib "easyedapro") (part "5.1kΩ"))
    )
    (comp (ref "R64")
      (value "5.1kΩ")
      (footprint "easyedapro:R0603")
      (fields
        (field (name "Manufacturer Part") "0603WAF5101T5E")
        (field (name "Manufacturer") "UNI-ROYAL(厚声)")
      )
      (libsource (lib "easyedapro") (part "5.1kΩ"))
    )
    (comp (ref "R_DRE")
      (value "DRE_ENABLE")
      (footprint "easyedapro:R0603")
      (libsource (lib "easyedapro") (part "DRE_ENABLE"))
    )
    (comp (ref "R_HP")
      (value "HP_ROUTER")
      (footprint "easyedapro:R0603")
      (libsource (lib "easyedapro") (part "HP_ROUTER"))
    )
    (comp (ref "SW1")
      (value "EC11E1534408")
      (footprint "easyedapro:SW-TH_EC11XXXXXXXX")
      (fields (field (name "Manufacturer") "ALPS Electric"))
      (libsource (lib "easyedapro") (part "EC11E1534408"))
    )
    (comp (ref "U1")
      (value "DSP_MODULE_PRO_PLACEHOLDER")
      (footprint "easyedapro:DSP_MODULE_PRO_FOOTPRINT")
      (libsource (lib "easyedapro") (part "DSP_MODULE_PRO_PLACEHOLDER"))
    )
    (comp (ref "U2")
      (value "TL072IDR")
      (footprint "easyedapro:SOIC-8_L5.0-W4.0-P1.27-LS6.0-BL")
      (fields (field (name "Manufacturer") "TI(德州仪器)"))
      (libsource (lib "easyedapro") (part "TL072IDR"))
    )
    (comp (ref "U3")
      (value "TPA6138A2PWR")
      (footprint "easyedapro:TSSOP-14_L5.0-W4.4-P0.65-LS6.4-BL")
      (fields (field (name "Manufacturer") "TI(德州仪器)"))
      (libsource (lib "easyedapro") (part "TPA6138A2PWR"))
    )
    (comp (ref "U4")
      (value "TL072IDR")
      (footprint "easyedapro:SOIC-8_L5.0-W4.0-P1.27-LS6.0-BL")
      (fields (field (name "Manufacturer") "TI(德州仪器)"))
      (libsource (lib "easyedapro") (part "TL072IDR"))
    )
    (comp (ref "U5")
      (value "TL072IDR")
      (footprint "easyedapro:SOIC-8_L5.0-W4.0-P1.27-LS6.0-BL")
      (fields (field (name "Manufacturer") "TI(德州仪器)"))
      (libsource (lib "easyedapro") (part "TL072IDR"))
    )
    (comp (ref "U7")
      (value "TL072IDR")
      (footprint "easyedapro:SOIC-8_L5.0-W4.0-P1.27-LS6.0-BL")
      (fields (field (name "Manufacturer") "TI(德州仪器)"))
      (libsource (lib "easyedapro") (part "TL072IDR"))
    )
    (comp (ref "U9")
      (value "AP3012KTR-G1")
      (footprint "easyedapro:TSOT-23-5_L2.9-W1.6-P0.95-LS2.8-BL")
      (fields (field (name "Manufacturer") "DIODES(美台)"))
      (libsource (lib "easyedapro") (part "AP3012KTR-G1"))
    )
    (comp (ref "USB2")
      (value "TYPE-C16PIN")
      (footprint "easyedapro:USB-C-SMD_TYPE-C16PIN")
      (fields (field (name "Manufacturer") "SHOU HAN(首韩)"))
      (libsource (lib "easyedapro") (part "TYPE-C16PIN"))
    )
  )
  (nets
    (net (code "1") (name "+5V") (class "Default")
      (node (ref "C27") (pin "2") (pinfunction "2_2") (pintype "unspecified"))
      (node (ref "C28") (pin "1") (pinfunction "1_1") (pintype "input"))
      (node (ref "D1") (pin "1") (pinfunction "-_1") (pintype "unspecified"))
      (node (ref "L12") (pin "2") (pinfunction "2_2") (pintype "unspecified"))
      (node (ref "L5") (pin "2") (pinfunction "2_2") (pintype "unspecified"))
      (node (ref "U9") (pin "4") (pinfunction "nSHDN_4") (pintype "unspecified"))
      (node (ref "U9") (pin "5") (pinfunction "VIN_5") (pintype "unspecified"))
    )
    (net (code "2") (name "3V3_JTAG") (class "Default")
      (node (ref "L1") (pin "1") (pinfunction "1_1") (pintype "unspecified"))
      (node (ref "L13") (pin "1") (pinfunction "1_1") (pintype "unspecified"))
      (node (ref "L7") (pin "2") (pinfunction "2_2") (pintype "unspecified"))
      (node (ref "R15") (pin "2") (pinfunction "2_2") (pintype "input"))
      (node (ref "R16") (pin "2") (pinfunction "2_2") (pintype "input"))
      (node (ref "R17") (pin "2") (pinfunction "2_2") (pintype "input"))
      (node (ref "R30") (pin "1") (pinfunction "1_1") (pintype "input"))
      (node (ref "R8") (pin "1") (pinfunction "1_1") (pintype "input"))
    )
    (net (code "3") (name "AGND") (class "Default")
      (node (ref "C69") (pin "2") (pinfunction "2_2") (pintype "input"))
      (node (ref "C75") (pin "2") (pinfunction "2_2") (pintype "input"))
      (node (ref "H2") (pin "6") (pinfunction "6_6") (pintype "unspecified"))
      (node (ref "R1") (pin "1") (pinfunction "1_1") (pintype "input"))
      (node (ref "R56") (pin "2") (pinfunction "2_2") (pintype "input"))
    )
    (net (code "4") (name "ANALOG_1") (class "Default")
      (node (ref "P1") (pin "16") (pinfunction "16_16") (pintype "input"))
    )
    (net (code "5") (name "ANALOG_2") (class "Default")
      (node (ref "P1") (pin "15") (pinfunction "15_15") (pintype "input"))
    )
    (net (code "6") (name "DEBUG_D+") (class "Default")
      (node (ref "P1") (pin "11") (pinfunction "11_11") (pintype "input"))
      (node (ref "USB2") (pin "A6") (pinfunction "DP1_A6") (pintype "unspecified"))
      (node (ref "USB2") (pin "B6") (pinfunction "DP2_B6") (pintype "unspecified"))
    )
    (net (code "7") (name "DEBUG_D-") (class "Default")
      (node (ref "P1") (pin "10") (pinfunction "10_10") (pintype "input"))
      (node (ref "USB2") (pin "A7") (pinfunction "DN1_A7") (pintype "unspecified"))
      (node (ref "USB2") (pin "B7") (pinfunction "DN2_B7") (pintype "unspecified"))
    )
    (net (code "8") (name "ESPR_READ") (class "Default")
      (node (ref "J3") (pin "4") (pinfunction "4_4") (pintype "input"))
      (node (ref "P1") (pin "9") (pinfunction "9_9") (pintype "input"))
    )
    (net (code "9") (name "FOOTSWITCH_READ") (class "Default")
      (node (ref "H1") (pin "1") (pinfunction "1_1") (pintype "unspecified"))
      (node (ref "P1") (pin "12") (pinfunction "12_12") (pintype "input"))
      (node (ref "R8") (pin "2") (pinfunction "2_2") (pintype "input"))
    )
    (net (code "10") (name "GND") (class "Default")
      (node (ref "C10") (pin "1") (pinfunction "1_1") (pintype "unspecified"))
      (node (ref "C11") (pin "1") (pinfunction "1_1") (pintype "unspecified"))
      (node (ref "C15") (pin "1") (pinfunction "1_1") (pintype "input"))
      (node (ref "C16") (pin "1") (pinfunction "1_1") (pintype "unspecified"))
      (node (ref "C18") (pin "1") (pinfunction "1_1") (pintype "unspecified"))
      (node (ref "C21") (pin "1") (pinfunction "1_1") (pintype "input"))
      (node (ref "C22") (pin "1") (pinfunction "1_1") (pintype "input"))
      (node (ref "C27") (pin "1") (pinfunction "1_1") (pintype "unspecified"))
      (node (ref "C28") (pin "2") (pinfunction "2_2") (pintype "input"))
      (node (ref "C3") (pin "1") (pinfunction "1_1") (pintype "unspecified"))
      (node (ref "C32") (pin "2") (pinfunction "2_2") (pintype "unspecified"))
      (node (ref "C35") (pin "1") (pinfunction "1_1") (pintype "unspecified"))
      (node (ref "C37") (pin "2") (pinfunction "2_2") (pintype "input"))
      (node (ref "C39") (pin "1") (pinfunction "1_1") (pintype "unspecified"))
      (node (ref "C4") (pin "1") (pinfunction "1_1") (pintype "unspecified"))
      (node (ref "C40") (pin "1") (pinfunction "1_1") (pintype "unspecified"))
      (node (ref "C41") (pin "1") (pinfunction "1_1") (pintype "input"))
      (node (ref "C42") (pin "2") (pinfunction "2_2") (pintype "unspecified"))
      (node (ref "C45") (pin "1") (pinfunction "1_1") (pintype "unspecified"))
      (node (ref "C46") (pin "1") (pinfunction "1_1") (pintype "input"))
      (node (ref "C48") (pin "1") (pinfunction "1_1") (pintype "input"))
      (node (ref "C5") (pin "1") (pinfunction "1_1") (pintype "input"))
      (node (ref "C50") (pin "2") (pinfunction "2_2") (pintype "input"))
      (node (ref "C55") (pin "2") (pinfunction "2_2") (pintype "input"))
      (node (ref "C6") (pin "2") (pinfunction "2_2") (pintype "input"))
      (node (ref "C60") (pin "2") (pinfunction "2_2") (pintype "input"))
      (node (ref "C61") (pin "2") (pinfunction "2_2") (pintype "input"))
      (node (ref "C62") (pin "2") (pinfunction "2_2") (pintype "input"))
      (node (ref "C63") (pin "2") (pinfunction "2_2") (pintype "input"))
      (node (ref "C66") (pin "2") (pinfunction "2_2") (pintype "input"))
      (node (ref "C67") (pin "2") (pinfunction "2_2") (pintype "input"))
      (node (ref "C8") (pin "1") (pinfunction "1_1") (pintype "input"))
      (node (ref "C9") (pin "1") (pinfunction "1_1") (pintype "unspecified"))
      (node (ref "DC2") (pin "1") (pinfunction "1_1") (pintype "unspecified"))
      (node (ref "H1") (pin "2") (pinfunction "2_2") (pintype "unspecified"))
      (node (ref "J2") (pin "2") (pinfunction "2_2") (pintype "input"))
      (node (ref "J3") (pin "2") (pinfunction "2_2") (pintype "input"))
      (node (ref "J4") (pin "2") (pinfunction "2_2") (pintype "input"))
      (node (ref "J5") (pin "2") (pinfunction "2_2") (pintype "unspecified"))
      (node (ref "J5") (pin "7") (pinfunction "7_7") (pintype "unspecified"))
      (node (ref "J6") (pin "2") (pinfunction "2_2") (pintype "unspecified"))
      (node (ref "J6") (pin "7") (pinfunction "7_7") (pintype "unspecified"))
      (node (ref "J7") (pin "2") (pinfunction "2_2") (pintype "unspecified"))
      (node (ref "J7") (pin "3") (pinfunction "3_3") (pintype "unspecified"))
      (node (ref "J8") (pin "2") (pinfunction "2_2") (pintype "unspecified"))
      (node (ref "J8") (pin "3") (pinfunction "3_3") (pintype "unspecified"))
      (node (ref "L10") (pin "2") (pinfunction "2_2") (pintype "unspecified"))
      (node (ref "L11") (pin "1") (pinfunction "1_1") (pintype "unspecified"))
      (node (ref "L14") (pin "2") (pinfunction "2_2") (pintype "unspecified"))
      (node (ref "L6") (pin "1") (pinfunction "1_1") (pintype "unspecified"))
      (node (ref "P1") (pin "40") (pinfunction "40_40") (pintype "input"))
      (node (ref "R3") (pin "1") (pinfunction "1_1") (pintype "input"))
      (node (ref "R31") (pin "1") (pinfunction "1_1") (pintype "input"))
      (node (ref "R32") (pin "1") (pinfunction "1_1") (pintype "input"))
      (node (ref "R38") (pin "1") (pinfunction "1_1") (pintype "input"))
      (node (ref "R54") (pin "1") (pinfunction "1_1") (pintype "input"))
      (node (ref "R55") (pin "1") (pinfunction "1_1") (pintype "input"))
      (node (ref "R63") (pin "1") (pinfunction "1_1") (pintype "input"))
      (node (ref "R64") (pin "1") (pinfunction "1_1") (pintype "input"))
      (node (ref "R7") (pin "1") (pinfunction "1_1") (pintype "input"))
      (node (ref "SW1") (pin "C") (pinfunction "C_C") (pintype "unspecified"))
      (node (ref "U2") (pin "4") (pinfunction "VCC-_4") (pintype "unspecified"))
      (node (ref "U3") (pin "10") (pinfunction "GND_10") (pintype "unspecified"))
      (node (ref "U3") (pin "4") (pinfunction "GND_4") (pintype "unspecified"))
      (node (ref "U4") (pin "4") (pinfunction "VCC-_4") (pintype "unspecified"))
      (node (ref "U5") (pin "4") (pinfunction "VCC-_4") (pintype "unspecified"))
      (node (ref "U7") (pin "4") (pinfunction "VCC-_4") (pintype "unspecified"))
      (node (ref "U9") (pin "2") (pinfunction "GND_2") (pintype "unspecified"))
      (node (ref "USB2") (pin "1") (pinfunction "SHELL_1") (pintype "unspecified"))
      (node (ref "USB2") (pin "2") (pinfunction "SHELL_2") (pintype "unspecified"))
      (node (ref "USB2") (pin "3") (pinfunction "SHELL_3") (pintype "unspecified"))
      (node (ref "USB2") (pin "4") (pinfunction "SHELL_4") (pintype "unspecified"))
      (node (ref "USB2") (pin "A1B12") (pinfunction "GND_A1B12") (pintype "unspecified"))
      (node (ref "USB2") (pin "B1A12") (pinfunction "GND_B1A12") (pintype "unspecified"))
    )
    (net (code "11") (name "GPIN_0") (class "Default")
      (node (ref "P1") (pin "22") (pinfunction "22_22") (pintype "input"))
      (node (ref "R17") (pin "1") (pinfunction "1_1") (pintype "input"))
      (node (ref "SW1") (pin "D") (pinfunction "D_D") (pintype "unspecified"))
    )
    (net (code "12") (name "GPIN_1") (class "Default")
      (node (ref "P1") (pin "21") (pinfunction "21_21") (pintype "input"))
      (node (ref "R16") (pin "1") (pinfunction "1_1") (pintype "input"))
      (node (ref "SW1") (pin "A") (pinfunction "A_A") (pintype "unspecified"))
    )
    (net (code "13") (name "GPIN_2") (class "Default")
      (node (ref "P1") (pin "24") (pinfunction "24_24") (pintype "input"))
    )
    (net (code "14") (name "GPIN_3") (class "Default")
      (node (ref "P1") (pin "23") (pinfunction "23_23") (pintype "input"))
      (node (ref "R15") (pin "1") (pinfunction "1_1") (pintype "input"))
      (node (ref "SW1") (pin "B") (pinfunction "B_B") (pintype "unspecified"))
    )
    (net (code "15") (name "GPOUT_0") (class "Default")
      (node (ref "P1") (pin "30") (pinfunction "30_30") (pintype "input"))
    )
    (net (code "16") (name "GPOUT_1") (class "Default")
      (node (ref "P1") (pin "29") (pinfunction "29_29") (pintype "input"))
    )
    (net (code "17") (name "GPOUT_2") (class "Default")
      (node (ref "P1") (pin "32") (pinfunction "32_32") (pintype "input"))
      (node (ref "R14") (pin "1") (pinfunction "1_1") (pintype "input"))
    )
    (net (code "18") (name "GPOUT_3") (class "Default")
      (node (ref "P1") (pin "31") (pinfunction "31_31") (pintype "input"))
    )
    (net (code "19") (name "GPOUT_4") (class "Default")
      (node (ref "P1") (pin "34") (pinfunction "34_34") (pintype "input"))
      (node (ref "R11") (pin "1") (pinfunction "1_1") (pintype "input"))
    )
    (net (code "20") (name "GPOUT_5") (class "Default")
      (node (ref "P1") (pin "35") (pinfunction "35_35") (pintype "input"))
    )
    (net (code "21") (name "GPOUT_6") (class "Default")
      (node (ref "P1") (pin "36") (pinfunction "36_36") (pintype "input"))
    )
    (net (code "22") (name "GPOUT_7") (class "Default")
      (node (ref "P1") (pin "33") (pinfunction "33_33") (pintype "input"))
      (node (ref "R13") (pin "1") (pinfunction "1_1") (pintype "input"))
    )
    (net (code "23") (name "HEADPHONES_L") (class "Default")
      (node (ref "L8") (pin "2") (pinfunction "2_2") (pintype "unspecified"))
      (node (ref "R29") (pin "2") (pinfunction "2_2") (pintype "input"))
      (node (ref "U3") (pin "12") (pinfunction "OUTL_12") (pintype "unspecified"))
    )
    (net (code "24") (name "HEADPHONES_R") (class "Default")
      (node (ref "L9") (pin "2") (pinfunction "2_2") (pintype "unspecified"))
      (node (ref "R12") (pin "1") (pinfunction "1_1") (pintype "input"))
      (node (ref "U3") (pin "3") (pinfunction "OUTR_3") (pintype "unspecified"))
    )
    (net (code "25") (name "HP_L") (class "Default")
      (node (ref "H2") (pin "2") (pinfunction "2_2") (pintype "unspecified"))
    )
    (net (code "26") (name "HP_R") (class "Default")
      (node (ref "H2") (pin "1") (pinfunction "1_1") (pintype "unspecified"))
    )
    (net (code "27") (name "HV_VCC") (class "Default")
      (node (ref "C35") (pin "2") (pinfunction "2_2") (pintype "unspecified"))
      (node (ref "C48") (pin "2") (pinfunction "2_2") (pintype "input"))
      (node (ref "D2") (pin "1") (pinfunction "-_1") (pintype "unspecified"))
      (node (ref "L2") (pin "1") (pinfunction "1_1") (pintype "unspecified"))
      (node (ref "R48") (pin "2") (pinfunction "2_2") (pintype "input"))
      (node (ref "R62") (pin "1") (pinfunction "1_1") (pintype "input"))
    )
    (net (code "28") (name "I2C_SCL") (class "Default")
      (node (ref "OLED1") (pin "3") (pinfunction "SCK_3") (pintype "unspecified"))
      (node (ref "P1") (pin "20") (pinfunction "20_20") (pintype "input"))
    )
    (net (code "29") (name "I2C_SDA") (class "Default")
      (node (ref "OLED1") (pin "4") (pinfunction "SDA_4") (pintype "unspecified"))
      (node (ref "P1") (pin "19") (pinfunction "19_19") (pintype "input"))
    )
    (net (code "30") (name "IN1_L") (class "Default")
      (node (ref "C57") (pin "2") (pinfunction "2_2") (pintype "input"))
      (node (ref "H2") (pin "8") (pinfunction "8_8") (pintype "unspecified"))
    )
    (net (code "31") (name "IN1_R") (class "Default")
      (node (ref "C56") (pin "2") (pinfunction "2_2") (pintype "input"))
      (node (ref "H2") (pin "7") (pinfunction "7_7") (pintype "unspecified"))
    )
    (net (code "32") (name "IN2_L") (class "Default")
      (node (ref "C59") (pin "2") (pinfunction "2_2") (pintype "input"))
      (node (ref "H2") (pin "10") (pinfunction "10_10") (pintype "unspecified"))
    )
    (net (code "33") (name "IN2_R") (class "Default")
      (node (ref "C58") (pin "2") (pinfunction "2_2") (pintype "input"))
      (node (ref "H2") (pin "9") (pinfunction "9_9") (pintype "unspecified"))
    )
    (net (code "34") (name "JACK_DETECT_L") (class "Default")
      (node (ref "J6") (pin "3") (pinfunction "3_3") (pintype "unspecified"))
      (node (ref "P1") (pin "37") (pinfunction "37_37") (pintype "input"))
    )
    (net (code "35") (name "JACK_DETECT_R") (class "Default")
      (node (ref "J5") (pin "3") (pinfunction "3_3") (pintype "unspecified"))
      (node (ref "P1") (pin "38") (pinfunction "38_38") (pintype "input"))
    )
    (net (code "36") (name "JOLLY_IN") (class "Default")
      (node (ref "P1") (pin "18") (pinfunction "18_18") (pintype "input"))
    )
    (net (code "37") (name "JOLLY_I{slash}O") (class "Default")
      (node (ref "P1") (pin "17") (pinfunction "17_17") (pintype "input"))
    )
    (net (code "38") (name "JTAG_GND") (class "Default")
      (node (ref "P1") (pin "14") (pinfunction "14_14") (pintype "input"))
    )
    (net (code "39") (name "MIDI_IN_4") (class "Default")
      (node (ref "J1") (pin "3") (pinfunction "3_3") (pintype "input"))
      (node (ref "P1") (pin "4") (pinfunction "4_4") (pintype "input"))
    )
    (net (code "40") (name "MIDI_IN_5") (class "Default")
      (node (ref "J1") (pin "4") (pinfunction "4_4") (pintype "input"))
      (node (ref "P1") (pin "3") (pinfunction "3_3") (pintype "input"))
    )
    (net (code "41") (name "MIDI_IN_ESP") (class "Default")
      (node (ref "P1") (pin "7") (pinfunction "7_7") (pintype "input"))
    )
    (net (code "42") (name "MIDI_OUT_4") (class "Default")
      (node (ref "J2") (pin "3") (pinfunction "3_3") (pintype "input"))
      (node (ref "P1") (pin "6") (pinfunction "6_6") (pintype "input"))
    )
    (net (code "43") (name "MIDI_OUT_5") (class "Default")
      (node (ref "J2") (pin "4") (pinfunction "4_4") (pintype "input"))
      (node (ref "P1") (pin "5") (pinfunction "5_5") (pintype "input"))
    )
    (net (code "44") (name "MIDI_OUT_ESP") (class "Default")
      (node (ref "P1") (pin "8") (pinfunction "8_8") (pintype "input"))
    )
    (net (code "45") (name "Net-(C39-Pad2)") (class "Default")
      (node (ref "C39") (pin "2") (pinfunction "2_2") (pintype "unspecified"))
      (node (ref "C40") (pin "2") (pinfunction "2_2") (pintype "unspecified"))
      (node (ref "C41") (pin "2") (pinfunction "2_2") (pintype "input"))
      (node (ref "C6") (pin "1") (pinfunction "1_1") (pintype "input"))
      (node (ref "L3") (pin "1") (pinfunction "1_1") (pintype "unspecified"))
      (node (ref "L4") (pin "1") (pinfunction "1_1") (pintype "unspecified"))
      (node (ref "P1") (pin "39") (pinfunction "39_39") (pintype "input"))
    )
    (net (code "46") (name "Net-(C56-Pad1)") (class "Default")
      (node (ref "C56") (pin "1") (pinfunction "1_1") (pintype "input"))
      (node (ref "R40") (pin "2") (pinfunction "2_2") (pintype "input"))
      (node (ref "R53") (pin "1") (pinfunction "1_1") (pintype "input"))
    )
    (net (code "47") (name "Net-(C57-Pad1)") (class "Default")
      (node (ref "C57") (pin "1") (pinfunction "1_1") (pintype "input"))
      (node (ref "R39") (pin "2") (pinfunction "2_2") (pintype "input"))
      (node (ref "R53") (pin "2") (pinfunction "2_2") (pintype "input"))
    )
    (net (code "48") (name "Net-(C58-Pad1)") (class "Default")
      (node (ref "C58") (pin "1") (pinfunction "1_1") (pintype "input"))
      (node (ref "R24") (pin "2") (pinfunction "2_2") (pintype "input"))
      (node (ref "R52") (pin "1") (pinfunction "1_1") (pintype "input"))
    )
    (net (code "49") (name "Net-(C59-Pad1)") (class "Default")
      (node (ref "C59") (pin "1") (pinfunction "1_1") (pintype "input"))
      (node (ref "R25") (pin "2") (pinfunction "2_2") (pintype "input"))
      (node (ref "R52") (pin "2") (pinfunction "2_2") (pintype "input"))
    )
    (net (code "50") (name "Net-(C60-Pad1)") (class "Default")
      (node (ref "C60") (pin "1") (pinfunction "1_1") (pintype "input"))
      (node (ref "R57") (pin "2") (pinfunction "2_2") (pintype "input"))
    )
    (net (code "51") (name "Net-(C61-Pad1)") (class "Default")
      (node (ref "C61") (pin "1") (pinfunction "1_1") (pintype "input"))
      (node (ref "R58") (pin "2") (pinfunction "2_2") (pintype "input"))
    )
    (net (code "52") (name "Net-(C64-Pad1)") (class "Default")
      (node (ref "C64") (pin "1") (pinfunction "1_1") (pintype "unspecified"))
      (node (ref "R35") (pin "1") (pinfunction "1_1") (pintype "input"))
    )
    (net (code "53") (name "Net-(C64-Pad2)") (class "Default")
      (node (ref "C64") (pin "2") (pinfunction "2_2") (pintype "unspecified"))
      (node (ref "J6") (pin "6") (pinfunction "6_6") (pintype "unspecified"))
    )
    (net (code "54") (name "Net-(C65-Pad1)") (class "Default")
      (node (ref "C65") (pin "1") (pinfunction "1_1") (pintype "unspecified"))
      (node (ref "R47") (pin "1") (pinfunction "1_1") (pintype "input"))
    )
    (net (code "55") (name "Net-(C65-Pad2)") (class "Default")
      (node (ref "C65") (pin "2") (pinfunction "2_2") (pintype "unspecified"))
      (node (ref "J5") (pin "6") (pinfunction "6_6") (pintype "unspecified"))
    )
    (net (code "56") (name "Net-(C68-Pad1)") (class "Default")
      (node (ref "C68") (pin "1") (pinfunction "1_1") (pintype "input"))
      (node (ref "R46") (pin "1") (pinfunction "1_1") (pintype "input"))
    )
    (net (code "57") (name "Net-(C69-Pad1)") (class "Default")
      (node (ref "C69") (pin "1") (pinfunction "1_1") (pintype "input"))
      (node (ref "R49") (pin "1") (pinfunction "1_1") (pintype "input"))
    )
    (net (code "58") (name "Net-(C70-Pad1)") (class "Default")
      (node (ref "C70") (pin "1") (pinfunction "1_1") (pintype "input"))
      (node (ref "R51") (pin "2") (pinfunction "2_2") (pintype "input"))
    )
    (net (code "59") (name "Net-(C70-Pad2)") (class "Default")
      (node (ref "C70") (pin "2") (pinfunction "2_2") (pintype "input"))
      (node (ref "J8") (pin "6") (pinfunction "6_6") (pintype "unspecified"))
      (node (ref "J8") (pin "7") (pinfunction "7_7") (pintype "unspecified"))
    )
    (net (code "60") (name "Net-(C71-Pad1)") (class "Default")
      (node (ref "C71") (pin "1") (pinfunction "1_1") (pintype "input"))
      (node (ref "R42") (pin "2") (pinfunction "2_2") (pintype "input"))
    )
    (net (code "61") (name "Net-(C71-Pad2)") (class "Default")
      (node (ref "C71") (pin "2") (pinfunction "2_2") (pintype "input"))
      (node (ref "J8") (pin "4") (pinfunction "4_4") (pintype "unspecified"))
      (node (ref "J8") (pin "5") (pinfunction "5_5") (pintype "unspecified"))
    )
    (net (code "62") (name "Net-(C72-Pad1)") (class "Default")
      (node (ref "C72") (pin "1") (pinfunction "1_1") (pintype "input"))
      (node (ref "R28") (pin "2") (pinfunction "2_2") (pintype "input"))
    )
    (net (code "63") (name "Net-(C72-Pad2)") (class "Default")
      (node (ref "C72") (pin "2") (pinfunction "2_2") (pintype "input"))
      (node (ref "J7") (pin "6") (pinfunction "6_6") (pintype "unspecified"))
      (node (ref "J7") (pin "7") (pinfunction "7_7") (pintype "unspecified"))
    )
    (net (code "64") (name "Net-(C73-Pad1)") (class "Default")
      (node (ref "C73") (pin "1") (pinfunction "1_1") (pintype "input"))
      (node (ref "R41") (pin "2") (pinfunction "2_2") (pintype "input"))
    )
    (net (code "65") (name "Net-(C73-Pad2)") (class "Default")
      (node (ref "C73") (pin "2") (pinfunction "2_2") (pintype "input"))
      (node (ref "J7") (pin "4") (pinfunction "4_4") (pintype "unspecified"))
      (node (ref "J7") (pin "5") (pinfunction "5_5") (pintype "unspecified"))
    )
    (net (code "66") (name "Net-(C74-Pad1)") (class "Default")
      (node (ref "C74") (pin "1") (pinfunction "1_1") (pintype "input"))
      (node (ref "R26") (pin "1") (pinfunction "1_1") (pintype "input"))
    )
    (net (code "67") (name "Net-(C75-Pad1)") (class "Default")
      (node (ref "C75") (pin "1") (pinfunction "1_1") (pintype "input"))
      (node (ref "R22") (pin "1") (pinfunction "1_1") (pintype "input"))
    )
    (net (code "68") (name "Net-(D2-+)") (class "Default")
      (node (ref "D2") (pin "2") (pinfunction "+_2") (pintype "unspecified"))
      (node (ref "L5") (pin "1") (pinfunction "1_1") (pintype "unspecified"))
      (node (ref "U9") (pin "1") (pinfunction "SW_1") (pintype "unspecified"))
    )
    (net (code "69") (name "Net-(J3-Pad3)") (class "Default")
      (node (ref "J3") (pin "3") (pinfunction "3_3") (pintype "input"))
      (node (ref "R30") (pin "2") (pinfunction "2_2") (pintype "input"))
    )
    (net (code "70") (name "Net-(J4-Pad3)") (class "Default")
      (node (ref "J4") (pin "3") (pinfunction "3_3") (pintype "input"))
      (node (ref "L9") (pin "1") (pinfunction "1_1") (pintype "unspecified"))
      (node (ref "R_HP") (pin "1") (pinfunction "1_1") (pintype "input"))
    )
    (net (code "71") (name "Net-(J4-Pad4)") (class "Default")
      (node (ref "J4") (pin "4") (pinfunction "4_4") (pintype "input"))
      (node (ref "L8") (pin "1") (pinfunction "1_1") (pintype "unspecified"))
      (node (ref "R_HP") (pin "2") (pinfunction "2_2") (pintype "input"))
    )
    (net (code "72") (name "Net-(L2-Pad2)") (class "Default")
      (node (ref "L2") (pin "2") (pinfunction "2_2") (pintype "unspecified"))
      (node (ref "R5") (pin "1") (pinfunction "1_1") (pintype "input"))
    )
    (net (code "73") (name "Net-(L10-Pad1)") (class "Default")
      (node (ref "L10") (pin "1") (pinfunction "1_1") (pintype "unspecified"))
      (node (ref "SW1") (pin "7") (pinfunction "7_7") (pintype "unspecified"))
    )
    (net (code "74") (name "Net-(L12-Pad1)") (class "Default")
      (node (ref "L12") (pin "1") (pinfunction "1_1") (pintype "unspecified"))
      (node (ref "L3") (pin "2") (pinfunction "2_2") (pintype "unspecified"))
      (node (ref "L4") (pin "2") (pinfunction "2_2") (pintype "unspecified"))
    )
    (net (code "75") (name "Net-(L13-Pad2)") (class "Default")
      (node (ref "L13") (pin "2") (pinfunction "2_2") (pintype "unspecified"))
      (node (ref "P1") (pin "13") (pinfunction "13_13") (pintype "input"))
    )
    (net (code "76") (name "Net-(L14-Pad1)") (class "Default")
      (node (ref "L14") (pin "1") (pinfunction "1_1") (pintype "unspecified"))
      (node (ref "SW1") (pin "E") (pinfunction "E_E") (pintype "unspecified"))
    )
    (net (code "77") (name "Net-(LED1--)") (class "Default")
      (node (ref "L6") (pin "2") (pinfunction "2_2") (pintype "unspecified"))
      (node (ref "LED1") (pin "2") (pinfunction "-_2") (pintype "unspecified"))
    )
    (net (code "78") (name "Net-(LED1-Pad1)") (class "Default")
      (node (ref "LED1") (pin "1") (pinfunction "1_1") (pintype "unspecified"))
      (node (ref "R11") (pin "2") (pinfunction "2_2") (pintype "input"))
    )
    (net (code "79") (name "Net-(LED1-Pad3)") (class "Default")
      (node (ref "LED1") (pin "3") (pinfunction "3_3") (pintype "unspecified"))
      (node (ref "R13") (pin "2") (pinfunction "2_2") (pintype "input"))
    )
    (net (code "80") (name "Net-(LED1-Pad4)") (class "Default")
      (node (ref "LED1") (pin "4") (pinfunction "4_4") (pintype "unspecified"))
      (node (ref "R14") (pin "2") (pinfunction "2_2") (pintype "input"))
    )
    (net (code "81") (name "Net-(OLED1-GND)") (class "Default")
      (node (ref "L11") (pin "2") (pinfunction "2_2") (pintype "unspecified"))
      (node (ref "OLED1") (pin "2") (pinfunction "GND_2") (pintype "unspecified"))
    )
    (net (code "82") (name "Net-(OLED1-VCC)") (class "Default")
      (node (ref "C3") (pin "2") (pinfunction "2_2") (pintype "unspecified"))
      (node (ref "C4") (pin "2") (pinfunction "2_2") (pintype "unspecified"))
      (node (ref "C5") (pin "2") (pinfunction "2_2") (pintype "input"))
      (node (ref "L1") (pin "2") (pinfunction "2_2") (pintype "unspecified"))
      (node (ref "OLED1") (pin "1") (pinfunction "VCC_1") (pintype "unspecified"))
    )
    (net (code "83") (name "Net-(U2A-IN1+)") (class "Default")
      (node (ref "R49") (pin "2") (pinfunction "2_2") (pintype "input"))
      (node (ref "R50") (pin "2") (pinfunction "2_2") (pintype "input"))
      (node (ref "U2") (pin "3") (pinfunction "IN1+_3") (pintype "unspecified"))
    )
    (net (code "84") (name "Net-(U2A-IN1-)") (class "Default")
      (node (ref "R45") (pin "2") (pinfunction "2_2") (pintype "input"))
      (node (ref "R46") (pin "2") (pinfunction "2_2") (pintype "input"))
      (node (ref "U2") (pin "2") (pinfunction "IN1-_2") (pintype "unspecified"))
    )
    (net (code "85") (name "Net-(U2A-OUT1)") (class "Default")
      (node (ref "R44") (pin "2") (pinfunction "2_2") (pintype "input"))
      (node (ref "R45") (pin "1") (pinfunction "1_1") (pintype "input"))
      (node (ref "R51") (pin "1") (pinfunction "1_1") (pintype "input"))
      (node (ref "U2") (pin "1") (pinfunction "OUT1_1") (pintype "output"))
    )
    (net (code "86") (name "Net-(U2B-IN2+)") (class "Default")
      (node (ref "C42") (pin "1") (pinfunction "1_1") (pintype "unspecified"))
      (node (ref "C67") (pin "1") (pinfunction "1_1") (pintype "input"))
      (node (ref "R23") (pin "2") (pinfunction "2_2") (pintype "input"))
      (node (ref "R32") (pin "2") (pinfunction "2_2") (pintype "input"))
      (node (ref "R50") (pin "1") (pinfunction "1_1") (pintype "input"))
      (node (ref "U2") (pin "5") (pinfunction "IN2+_5") (pintype "unspecified"))
    )
    (net (code "87") (name "Net-(U2B-IN2-)") (class "Default")
      (node (ref "R43") (pin "2") (pinfunction "2_2") (pintype "input"))
      (node (ref "R44") (pin "1") (pinfunction "1_1") (pintype "input"))
      (node (ref "U2") (pin "6") (pinfunction "IN2-_6") (pintype "unspecified"))
    )
    (net (code "88") (name "Net-(U2B-OUT2)") (class "Default")
      (node (ref "R42") (pin "1") (pinfunction "1_1") (pintype "input"))
      (node (ref "R43") (pin "1") (pinfunction "1_1") (pintype "input"))
      (node (ref "U2") (pin "7") (pinfunction "OUT2_7") (pintype "output"))
    )
    (net (code "89") (name "Net-(U3-+INL)") (class "Default")
      (node (ref "R55") (pin "2") (pinfunction "2_2") (pintype "input"))
      (node (ref "R56") (pin "1") (pinfunction "1_1") (pintype "input"))
      (node (ref "U3") (pin "14") (pinfunction "+INL_14") (pintype "unspecified"))
    )
    (net (code "90") (name "Net-(U3-+INR)") (class "Default")
      (node (ref "R1") (pin "2") (pinfunction "2_2") (pintype "input"))
      (node (ref "R54") (pin "2") (pinfunction "2_2") (pintype "input"))
      (node (ref "U3") (pin "1") (pinfunction "+INR_1") (pintype "unspecified"))
    )
    (net (code "91") (name "Net-(U3--INL)") (class "Default")
      (node (ref "R29") (pin "1") (pinfunction "1_1") (pintype "input"))
      (node (ref "R59") (pin "1") (pinfunction "1_1") (pintype "input"))
      (node (ref "U3") (pin "13") (pinfunction "-INL_13") (pintype "unspecified"))
    )
    (net (code "92") (name "Net-(U3--INR)") (class "Default")
      (node (ref "R12") (pin "2") (pinfunction "2_2") (pintype "input"))
      (node (ref "R2") (pin "2") (pinfunction "2_2") (pintype "input"))
      (node (ref "U3") (pin "2") (pinfunction "-INR_2") (pintype "unspecified"))
    )
    (net (code "93") (name "Net-(U3-CN)") (class "Default")
      (node (ref "C49") (pin "1") (pinfunction "1_1") (pintype "input"))
      (node (ref "U3") (pin "7") (pinfunction "CN_7") (pintype "unspecified"))
    )
    (net (code "94") (name "Net-(U3-CP)") (class "Default")
      (node (ref "C49") (pin "2") (pinfunction "2_2") (pintype "input"))
      (node (ref "U3") (pin "8") (pinfunction "CP_8") (pintype "unspecified"))
    )
    (net (code "95") (name "Net-(U3-MUTE#)") (class "Default")
      (node (ref "C50") (pin "1") (pinfunction "1_1") (pintype "input"))
      (node (ref "L7") (pin "1") (pinfunction "1_1") (pintype "unspecified"))
      (node (ref "U3") (pin "5") (pinfunction "MUTE#_5") (pintype "unspecified"))
      (node (ref "U3") (pin "9") (pinfunction "VDD_9") (pintype "unspecified"))
    )
    (net (code "96") (name "Net-(U3-VSS)") (class "Default")
      (node (ref "C37") (pin "1") (pinfunction "1_1") (pintype "input"))
      (node (ref "U3") (pin "6") (pinfunction "VSS_6") (pintype "unspecified"))
    )
    (net (code "97") (name "Net-(U4A-IN1+)") (class "Default")
      (node (ref "R19") (pin "2") (pinfunction "2_2") (pintype "input"))
      (node (ref "R22") (pin "2") (pinfunction "2_2") (pintype "input"))
      (node (ref "U4") (pin "3") (pinfunction "IN1+_3") (pintype "unspecified"))
    )
    (net (code "98") (name "Net-(U4A-IN1-)") (class "Default")
      (node (ref "R26") (pin "2") (pinfunction "2_2") (pintype "input"))
      (node (ref "R27") (pin "2") (pinfunction "2_2") (pintype "input"))
      (node (ref "U4") (pin "2") (pinfunction "IN1-_2") (pintype "unspecified"))
    )
    (net (code "99") (name "Net-(U4A-OUT1)") (class "Default")
      (node (ref "R27") (pin "1") (pinfunction "1_1") (pintype "input"))
      (node (ref "R28") (pin "1") (pinfunction "1_1") (pintype "input"))
      (node (ref "R33") (pin "2") (pinfunction "2_2") (pintype "input"))
      (node (ref "U4") (pin "1") (pinfunction "OUT1_1") (pintype "output"))
    )
    (net (code "100") (name "Net-(U4B-IN2+)") (class "Default")
      (node (ref "C32") (pin "1") (pinfunction "1_1") (pintype "unspecified"))
      (node (ref "C66") (pin "1") (pinfunction "1_1") (pintype "input"))
      (node (ref "R18") (pin "2") (pinfunction "2_2") (pintype "input"))
      (node (ref "R19") (pin "1") (pinfunction "1_1") (pintype "input"))
      (node (ref "R31") (pin "2") (pinfunction "2_2") (pintype "input"))
      (node (ref "U4") (pin "5") (pinfunction "IN2+_5") (pintype "unspecified"))
    )
    (net (code "101") (name "Net-(U4B-IN2-)") (class "Default")
      (node (ref "R33") (pin "1") (pinfunction "1_1") (pintype "input"))
      (node (ref "R34") (pin "2") (pinfunction "2_2") (pintype "input"))
      (node (ref "U4") (pin "6") (pinfunction "IN2-_6") (pintype "unspecified"))
    )
    (net (code "102") (name "Net-(U4B-OUT2)") (class "Default")
      (node (ref "R34") (pin "1") (pinfunction "1_1") (pintype "input"))
      (node (ref "R41") (pin "1") (pinfunction "1_1") (pintype "input"))
      (node (ref "U4") (pin "7") (pinfunction "OUT2_7") (pintype "output"))
    )
    (net (code "103") (name "Net-(U5A-IN1+)") (class "Default")
      (node (ref "R10") (pin "2") (pinfunction "2_2") (pintype "input"))
      (node (ref "R47") (pin "2") (pinfunction "2_2") (pintype "input"))
      (node (ref "R_DRE") (pin "2") (pinfunction "2_2") (pintype "input"))
      (node (ref "U5") (pin "3") (pinfunction "IN1+_3") (pintype "unspecified"))
    )
    (net (code "104") (name "Net-(U5A-IN1-)") (class "Default")
      (node (ref "R57") (pin "1") (pinfunction "1_1") (pintype "input"))
      (node (ref "R60") (pin "1") (pinfunction "1_1") (pintype "input"))
      (node (ref "U5") (pin "2") (pinfunction "IN1-_2") (pintype "unspecified"))
    )
    (net (code "105") (name "Net-(U5A-OUT1)") (class "Default")
      (node (ref "R20") (pin "2") (pinfunction "2_2") (pintype "input"))
      (node (ref "R24") (pin "1") (pinfunction "1_1") (pintype "input"))
      (node (ref "R60") (pin "2") (pinfunction "2_2") (pintype "input"))
      (node (ref "U5") (pin "1") (pinfunction "OUT1_1") (pintype "output"))
    )
    (net (code "106") (name "Net-(U5B-IN2-)") (class "Default")
      (node (ref "R20") (pin "1") (pinfunction "1_1") (pintype "input"))
      (node (ref "R21") (pin "2") (pinfunction "2_2") (pintype "input"))
      (node (ref "U5") (pin "6") (pinfunction "IN2-_6") (pintype "unspecified"))
    )
    (net (code "107") (name "Net-(U5B-OUT2)") (class "Default")
      (node (ref "R21") (pin "1") (pinfunction "1_1") (pintype "input"))
      (node (ref "R25") (pin "1") (pinfunction "1_1") (pintype "input"))
      (node (ref "U5") (pin "7") (pinfunction "OUT2_7") (pintype "output"))
    )
    (net (code "108") (name "Net-(U7A-IN1+)") (class "Default")
      (node (ref "R35") (pin "2") (pinfunction "2_2") (pintype "input"))
      (node (ref "R9") (pin "2") (pinfunction "2_2") (pintype "input"))
      (node (ref "U7") (pin "3") (pinfunction "IN1+_3") (pintype "unspecified"))
    )
    (net (code "109") (name "Net-(U7A-IN1-)") (class "Default")
      (node (ref "R58") (pin "1") (pinfunction "1_1") (pintype "input"))
      (node (ref "R61") (pin "1") (pinfunction "1_1") (pintype "input"))
      (node (ref "U7") (pin "2") (pinfunction "IN1-_2") (pintype "unspecified"))
    )
    (net (code "110") (name "Net-(U7A-OUT1)") (class "Default")
      (node (ref "R37") (pin "2") (pinfunction "2_2") (pintype "input"))
      (node (ref "R40") (pin "1") (pinfunction "1_1") (pintype "input"))
      (node (ref "R61") (pin "2") (pinfunction "2_2") (pintype "input"))
      (node (ref "R_DRE") (pin "1") (pinfunction "1_1") (pintype "input"))
      (node (ref "U7") (pin "1") (pinfunction "OUT1_1") (pintype "output"))
    )
    (net (code "111") (name "Net-(U7B-IN2-)") (class "Default")
      (node (ref "R36") (pin "2") (pinfunction "2_2") (pintype "input"))
      (node (ref "R37") (pin "1") (pinfunction "1_1") (pintype "input"))
      (node (ref "U7") (pin "6") (pinfunction "IN2-_6") (pintype "unspecified"))
    )
    (net (code "112") (name "Net-(U7B-OUT2)") (class "Default")
      (node (ref "R36") (pin "1") (pinfunction "1_1") (pintype "input"))
      (node (ref "R39") (pin "1") (pinfunction "1_1") (pintype "input"))
      (node (ref "U7") (pin "7") (pinfunction "OUT2_7") (pintype "output"))
    )
    (net (code "113") (name "Net-(U9-FB)") (class "Default")
      (node (ref "R38") (pin "2") (pinfunction "2_2") (pintype "input"))
      (node (ref "R48") (pin "1") (pinfunction "1_1") (pintype "input"))
      (node (ref "R62") (pin "2") (pinfunction "2_2") (pintype "input"))
      (node (ref "U9") (pin "3") (pinfunction "FB_3") (pintype "unspecified"))
    )
    (net (code "114") (name "Net-(USB2-CC1)") (class "Default")
      (node (ref "R64") (pin "2") (pinfunction "2_2") (pintype "input"))
      (node (ref "USB2") (pin "A5") (pinfunction "CC1_A5") (pintype "unspecified"))
    )
    (net (code "115") (name "Net-(USB2-CC2)") (class "Default")
      (node (ref "R63") (pin "2") (pinfunction "2_2") (pintype "input"))
      (node (ref "USB2") (pin "B5") (pinfunction "CC2_B5") (pintype "unspecified"))
    )
    (net (code "116") (name "OPAMP_BIAS_L") (class "Default")
      (node (ref "C18") (pin "2") (pinfunction "2_2") (pintype "unspecified"))
      (node (ref "C62") (pin "1") (pinfunction "1_1") (pintype "input"))
      (node (ref "R10") (pin "1") (pinfunction "1_1") (pintype "input"))
      (node (ref "R6") (pin "2") (pinfunction "2_2") (pintype "input"))
      (node (ref "R7") (pin "2") (pinfunction "2_2") (pintype "input"))
      (node (ref "U5") (pin "5") (pinfunction "IN2+_5") (pintype "unspecified"))
    )
    (net (code "117") (name "OPAMP_BIAS_R") (class "Default")
      (node (ref "C11") (pin "2") (pinfunction "2_2") (pintype "unspecified"))
      (node (ref "C63") (pin "1") (pinfunction "1_1") (pintype "input"))
      (node (ref "R3") (pin "2") (pinfunction "2_2") (pintype "input"))
      (node (ref "R4") (pin "2") (pinfunction "2_2") (pintype "input"))
      (node (ref "R9") (pin "1") (pinfunction "1_1") (pintype "input"))
      (node (ref "U7") (pin "5") (pinfunction "IN2+_5") (pintype "unspecified"))
    )
    (net (code "118") (name "OPAMP_VCC") (class "Default")
      (node (ref "C10") (pin "2") (pinfunction "2_2") (pintype "unspecified"))
      (node (ref "C15") (pin "2") (pinfunction "2_2") (pintype "input"))
      (node (ref "C16") (pin "2") (pinfunction "2_2") (pintype "unspecified"))
      (node (ref "C21") (pin "2") (pinfunction "2_2") (pintype "input"))
      (node (ref "C22") (pin "2") (pinfunction "2_2") (pintype "input"))
      (node (ref "C45") (pin "2") (pinfunction "2_2") (pintype "unspecified"))
      (node (ref "C46") (pin "2") (pinfunction "2_2") (pintype "input"))
      (node (ref "C55") (pin "1") (pinfunction "1_1") (pintype "input"))
      (node (ref "C8") (pin "2") (pinfunction "2_2") (pintype "input"))
      (node (ref "C9") (pin "2") (pinfunction "2_2") (pintype "unspecified"))
      (node (ref "R18") (pin "1") (pinfunction "1_1") (pintype "input"))
      (node (ref "R23") (pin "1") (pinfunction "1_1") (pintype "input"))
      (node (ref "R4") (pin "1") (pinfunction "1_1") (pintype "input"))
      (node (ref "R5") (pin "2") (pinfunction "2_2") (pintype "input"))
      (node (ref "R6") (pin "1") (pinfunction "1_1") (pintype "input"))
      (node (ref "U2") (pin "8") (pinfunction "VCC+_8") (pintype "unspecified"))
      (node (ref "U4") (pin "8") (pinfunction "VCC+_8") (pintype "unspecified"))
      (node (ref "U5") (pin "8") (pinfunction "VCC+_8") (pintype "unspecified"))
      (node (ref "U7") (pin "8") (pinfunction "VCC+_8") (pintype "unspecified"))
    )
    (net (code "119") (name "OUT_L") (class "Default")
      (node (ref "C68") (pin "2") (pinfunction "2_2") (pintype "input"))
      (node (ref "H2") (pin "4") (pinfunction "4_4") (pintype "unspecified"))
      (node (ref "R59") (pin "2") (pinfunction "2_2") (pintype "input"))
    )
    (net (code "120") (name "OUT_R") (class "Default")
      (node (ref "C74") (pin "2") (pinfunction "2_2") (pintype "input"))
      (node (ref "H2") (pin "3") (pinfunction "3_3") (pintype "unspecified"))
      (node (ref "R2") (pin "1") (pinfunction "1_1") (pintype "input"))
    )
    (net (code "121") (name "SR_CLOCK") (class "Default")
      (node (ref "P1") (pin "25") (pinfunction "25_25") (pintype "input"))
    )
    (net (code "122") (name "SR_CS") (class "Default")
      (node (ref "P1") (pin "28") (pinfunction "28_28") (pintype "input"))
    )
    (net (code "123") (name "SR_SERIAL_IN") (class "Default")
      (node (ref "P1") (pin "26") (pinfunction "26_26") (pintype "input"))
    )
    (net (code "124") (name "SR_SERIAL_OUT") (class "Default")
      (node (ref "P1") (pin "27") (pinfunction "27_27") (pintype "input"))
    )
    (net (code "125") (name "VDD_IN_PAD") (class "Default")
      (node (ref "D1") (pin "2") (pinfunction "+_2") (pintype "unspecified"))
      (node (ref "DC2") (pin "2") (pinfunction "2_2") (pintype "unspecified"))
      (node (ref "DC2") (pin "3") (pinfunction "3_3") (pintype "unspecified"))
    )
    (net (code "126") (name "unconnected-(H2-Pad5)") (class "Default")
      (node (ref "H2") (pin "5") (pinfunction "5_5") (pintype "unspecified+no_connect"))
    )
    (net (code "127") (name "unconnected-(H3-Pad1)") (class "Default")
      (node (ref "H3") (pin "1") (pinfunction "1_1") (pintype "unspecified+no_connect"))
    )
    (net (code "128") (name "unconnected-(H3-Pad2)") (class "Default")
      (node (ref "H3") (pin "2") (pinfunction "2_2") (pintype "unspecified+no_connect"))
    )
    (net (code "129") (name "unconnected-(J1-Pad2)") (class "Default")
      (node (ref "J1") (pin "2") (pinfunction "2_2") (pintype "input+no_connect"))
    )
    (net (code "130") (name "unconnected-(J5-Pad4)") (class "Default")
      (node (ref "J5") (pin "4") (pinfunction "4_4") (pintype "unspecified+no_connect"))
    )
    (net (code "131") (name "unconnected-(J5-Pad5)") (class "Default")
      (node (ref "J5") (pin "5") (pinfunction "5_5") (pintype "unspecified+no_connect"))
    )
    (net (code "132") (name "unconnected-(J6-Pad4)") (class "Default")
      (node (ref "J6") (pin "4") (pinfunction "4_4") (pintype "unspecified+no_connect"))
    )
    (net (code "133") (name "unconnected-(J6-Pad5)") (class "Default")
      (node (ref "J6") (pin "5") (pinfunction "5_5") (pintype "unspecified+no_connect"))
    )
    (net (code "134") (name "unconnected-(P1-Pad1)") (class "Default")
      (node (ref "P1") (pin "1") (pinfunction "1_1") (pintype "input+no_connect"))
    )
    (net (code "135") (name "unconnected-(P1-Pad2)") (class "Default")
      (node (ref "P1") (pin "2") (pinfunction "2_2") (pintype "input+no_connect"))
    )
    (net (code "136") (name "unconnected-(SW1-Pad6)") (class "Default")
      (node (ref "SW1") (pin "6") (pinfunction "6_6") (pintype "unspecified+no_connect"))
    )
    (net (code "137") (name "unconnected-(U3-UVP-Pad11)") (class "Default")
      (node (ref "U3") (pin "11") (pinfunction "UVP_11") (pintype "unspecified+no_connect"))
    )
    (net (code "138") (name "unconnected-(USB2-SBU1-PadA8)") (class "Default")
      (node (ref "USB2") (pin "A8") (pinfunction "SBU1_A8") (pintype "unspecified+no_connect"))
    )
    (net (code "139") (name "unconnected-(USB2-SBU2-PadB8)") (class "Default")
      (node (ref "USB2") (pin "B8") (pinfunction "SBU2_B8") (pintype "unspecified+no_connect"))
    )
    (net (code "140") (name "unconnected-(USB2-VBUS-PadA4B9)") (class "Default")
      (node (ref "USB2") (pin "A4B9") (pinfunction "VBUS_A4B9") (pintype "unspecified+no_connect"))
    )
    (net (code "141") (name "unconnected-(USB2-VBUS-PadB4A9)") (class "Default")
      (node (ref "USB2") (pin "B4A9") (pinfunction "VBUS_B4A9") (pintype "unspecified+no_connect"))
    )
  )
)
